# master_schematic.net
KiCad netlist of a schematic drawn in EAGLE
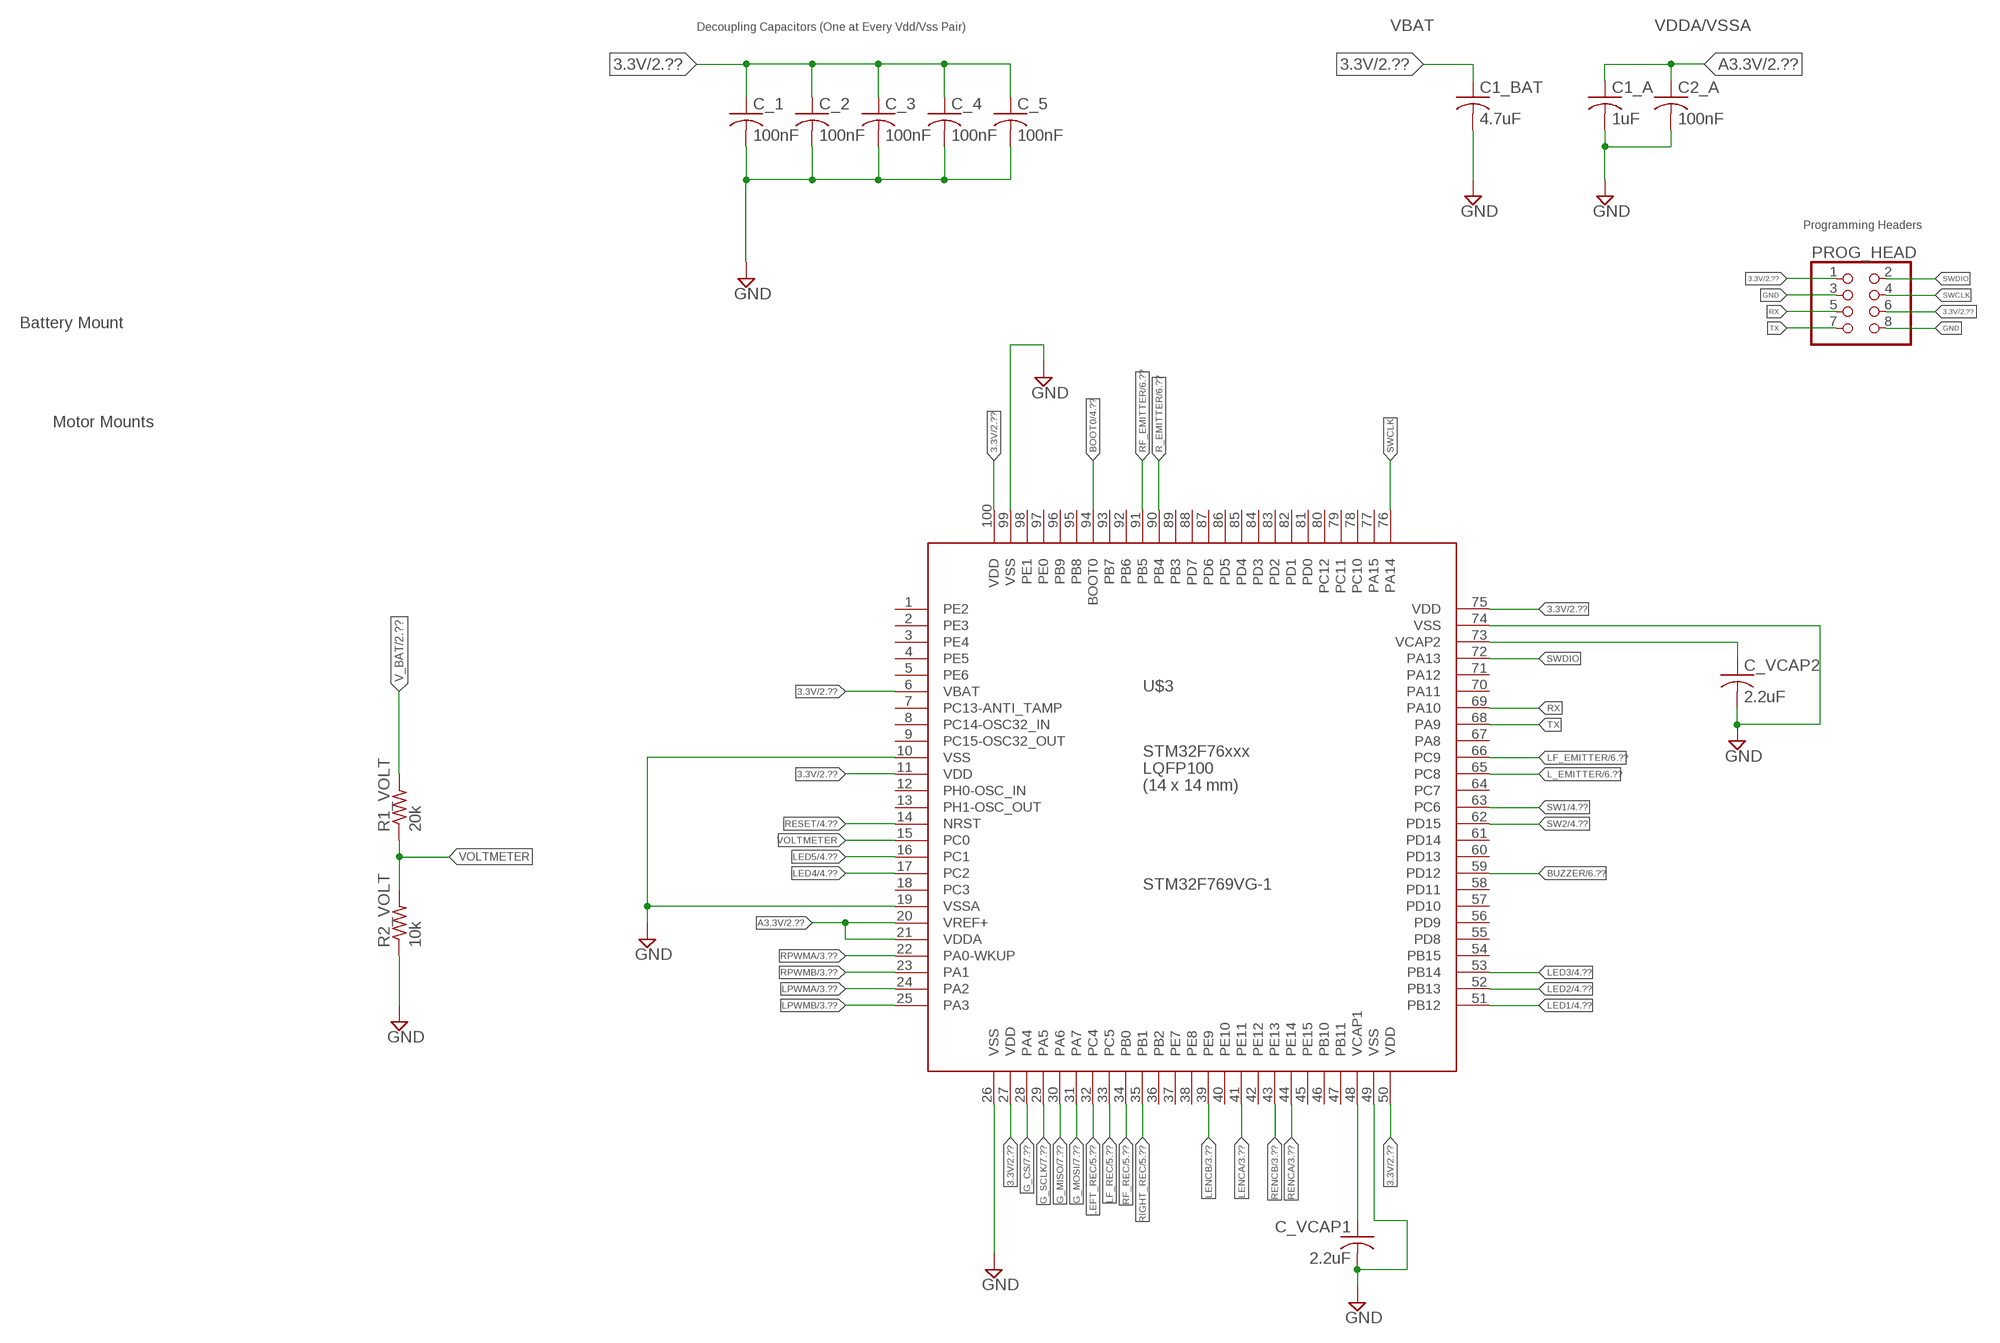
[diagram p0: schematic, sheet 1]
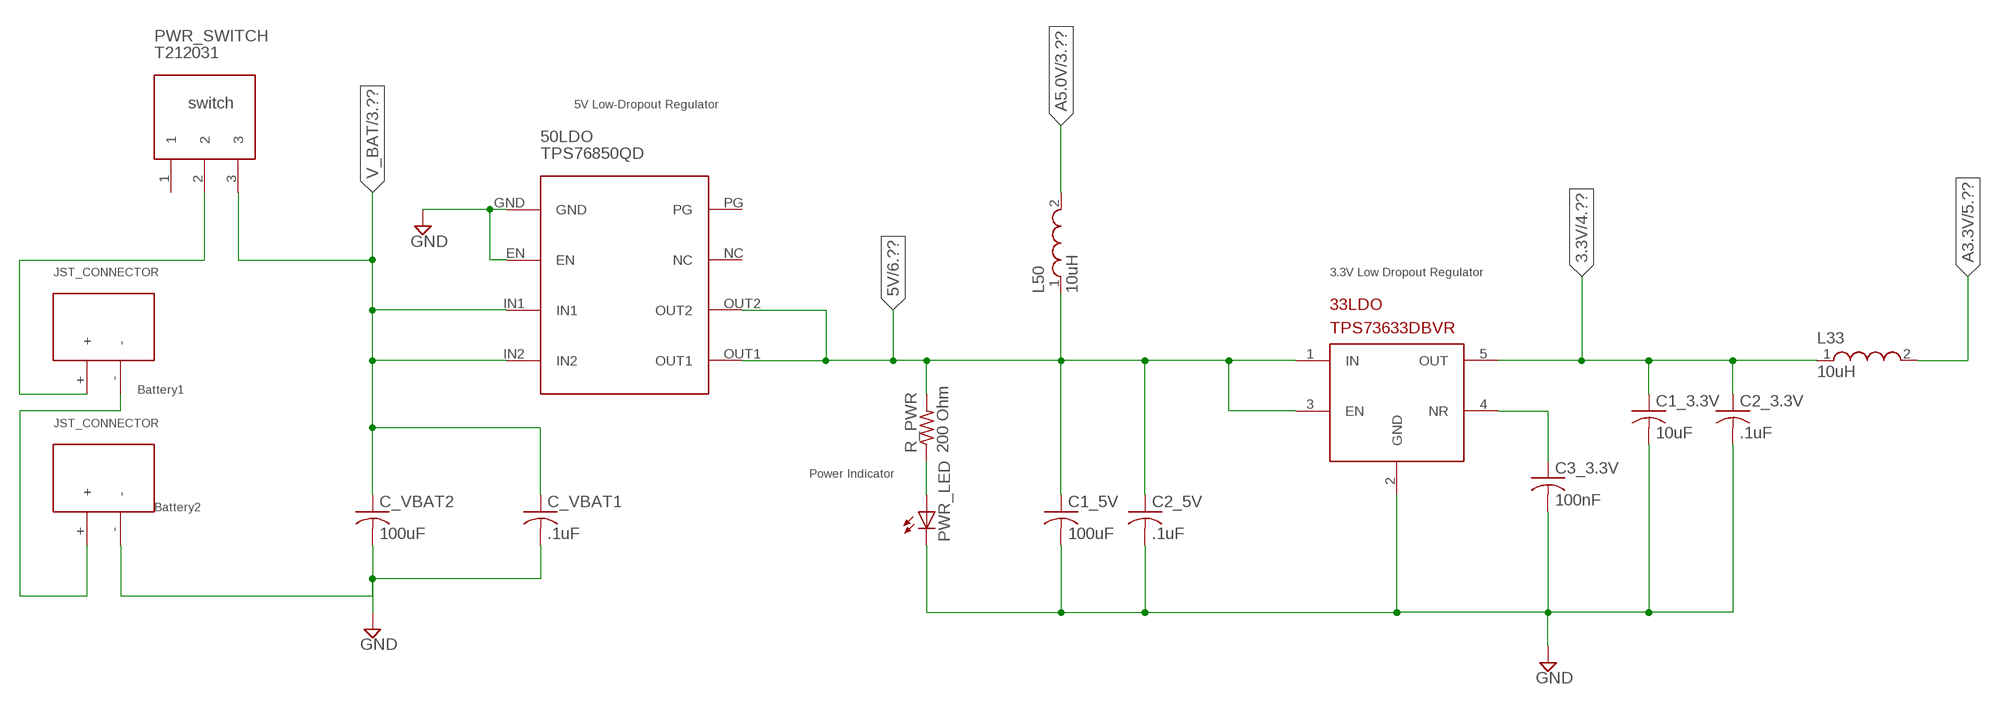
[diagram p1: schematic, sheet 2]
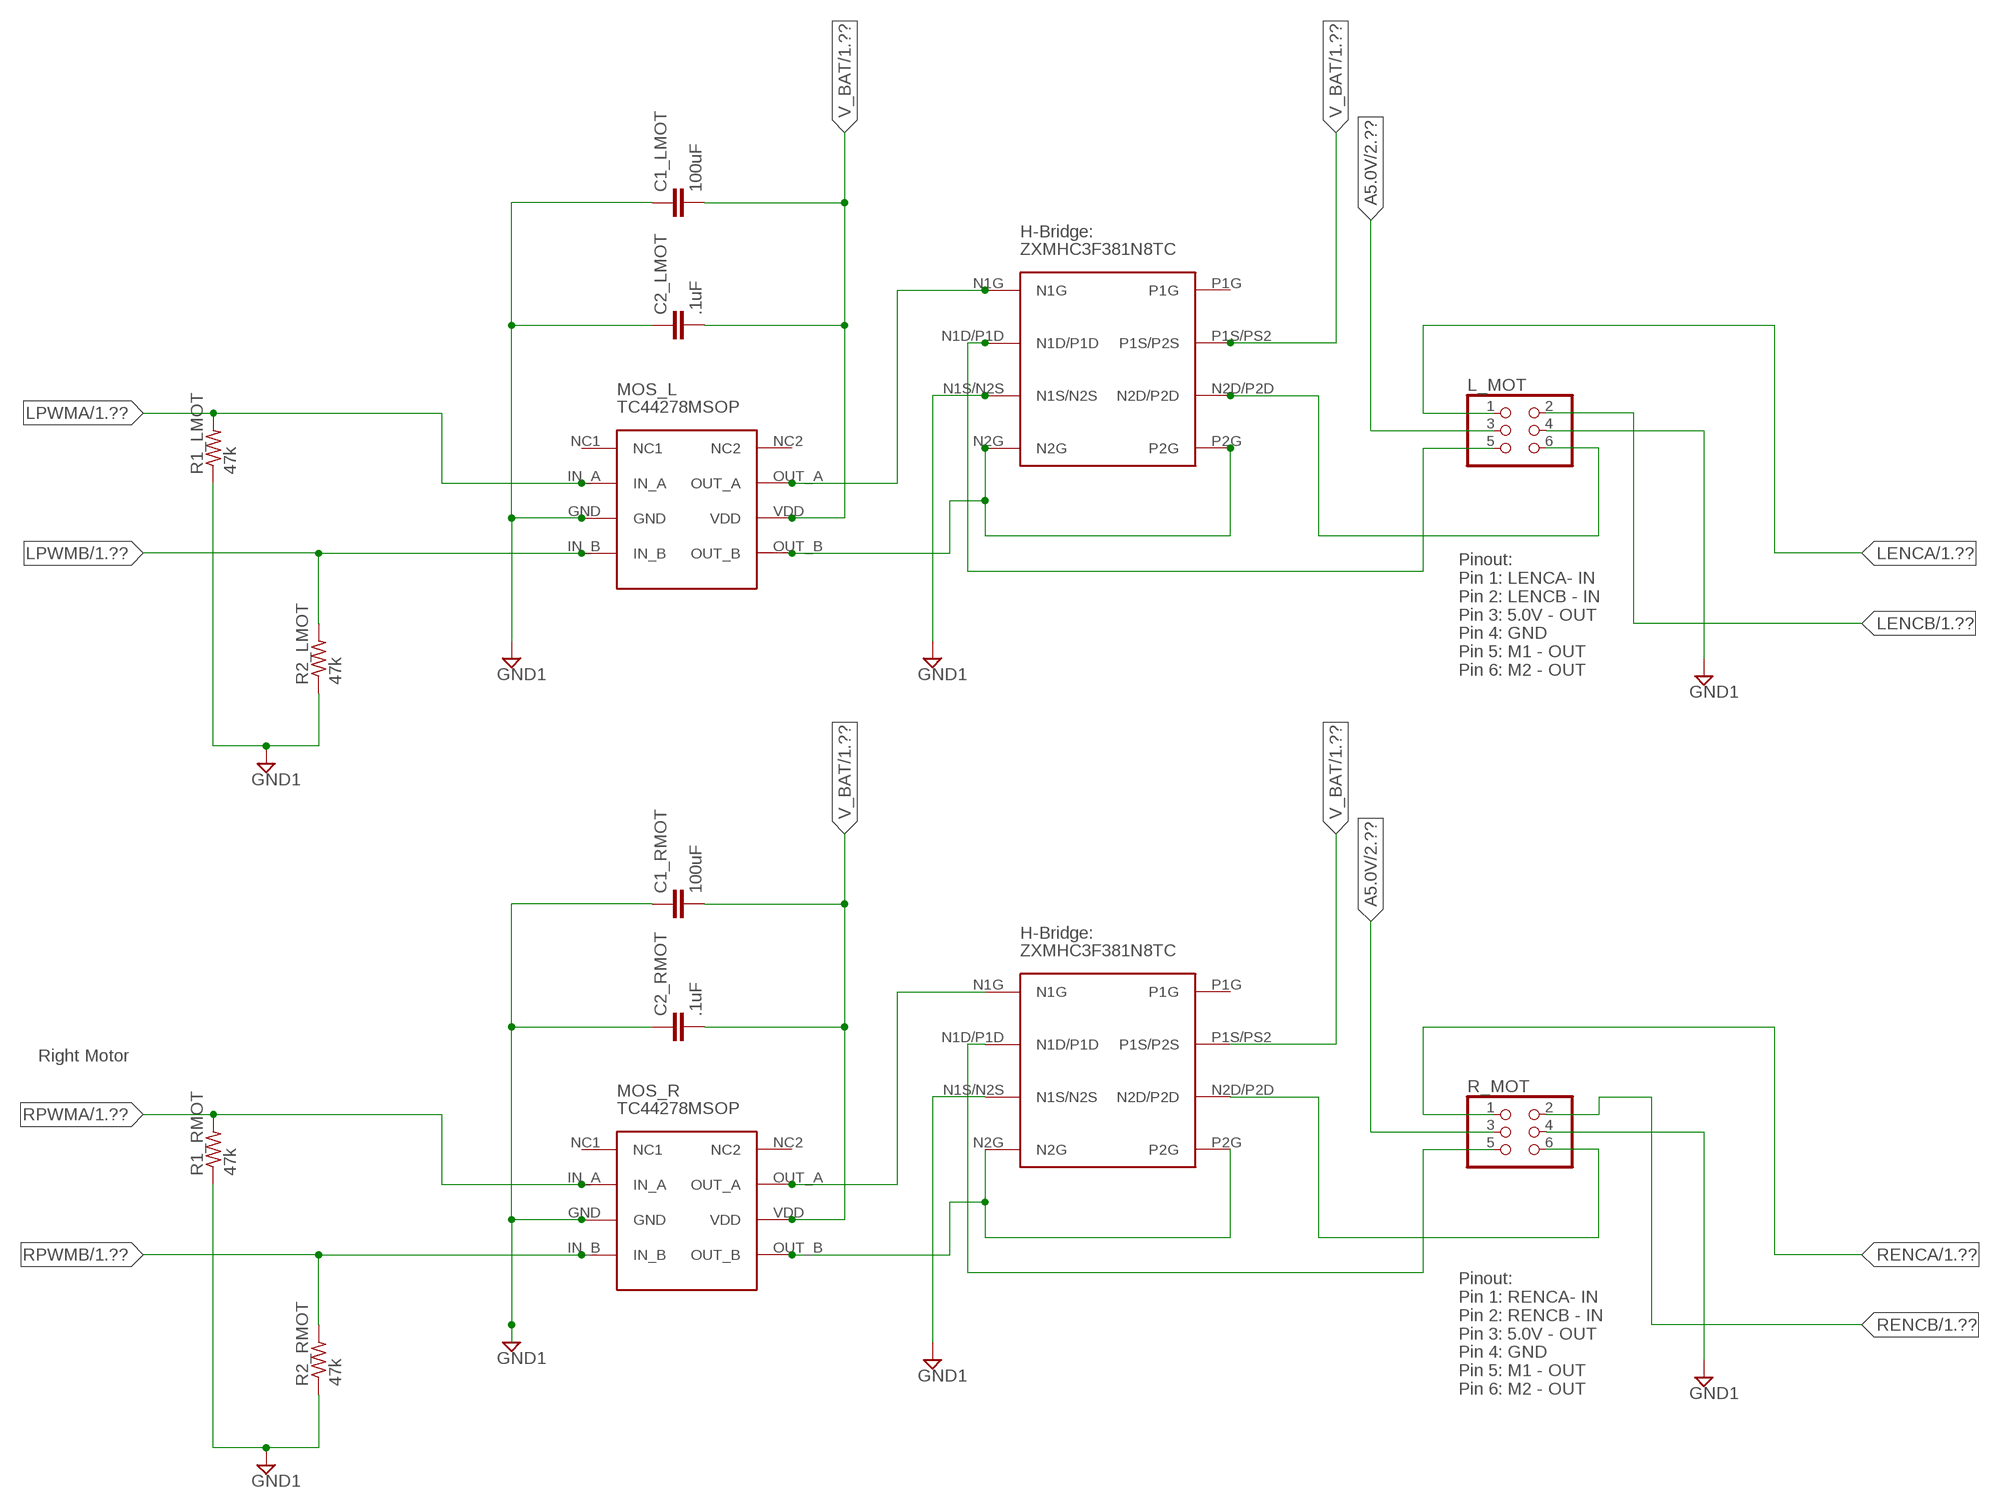
[diagram p2: schematic, sheet 3]
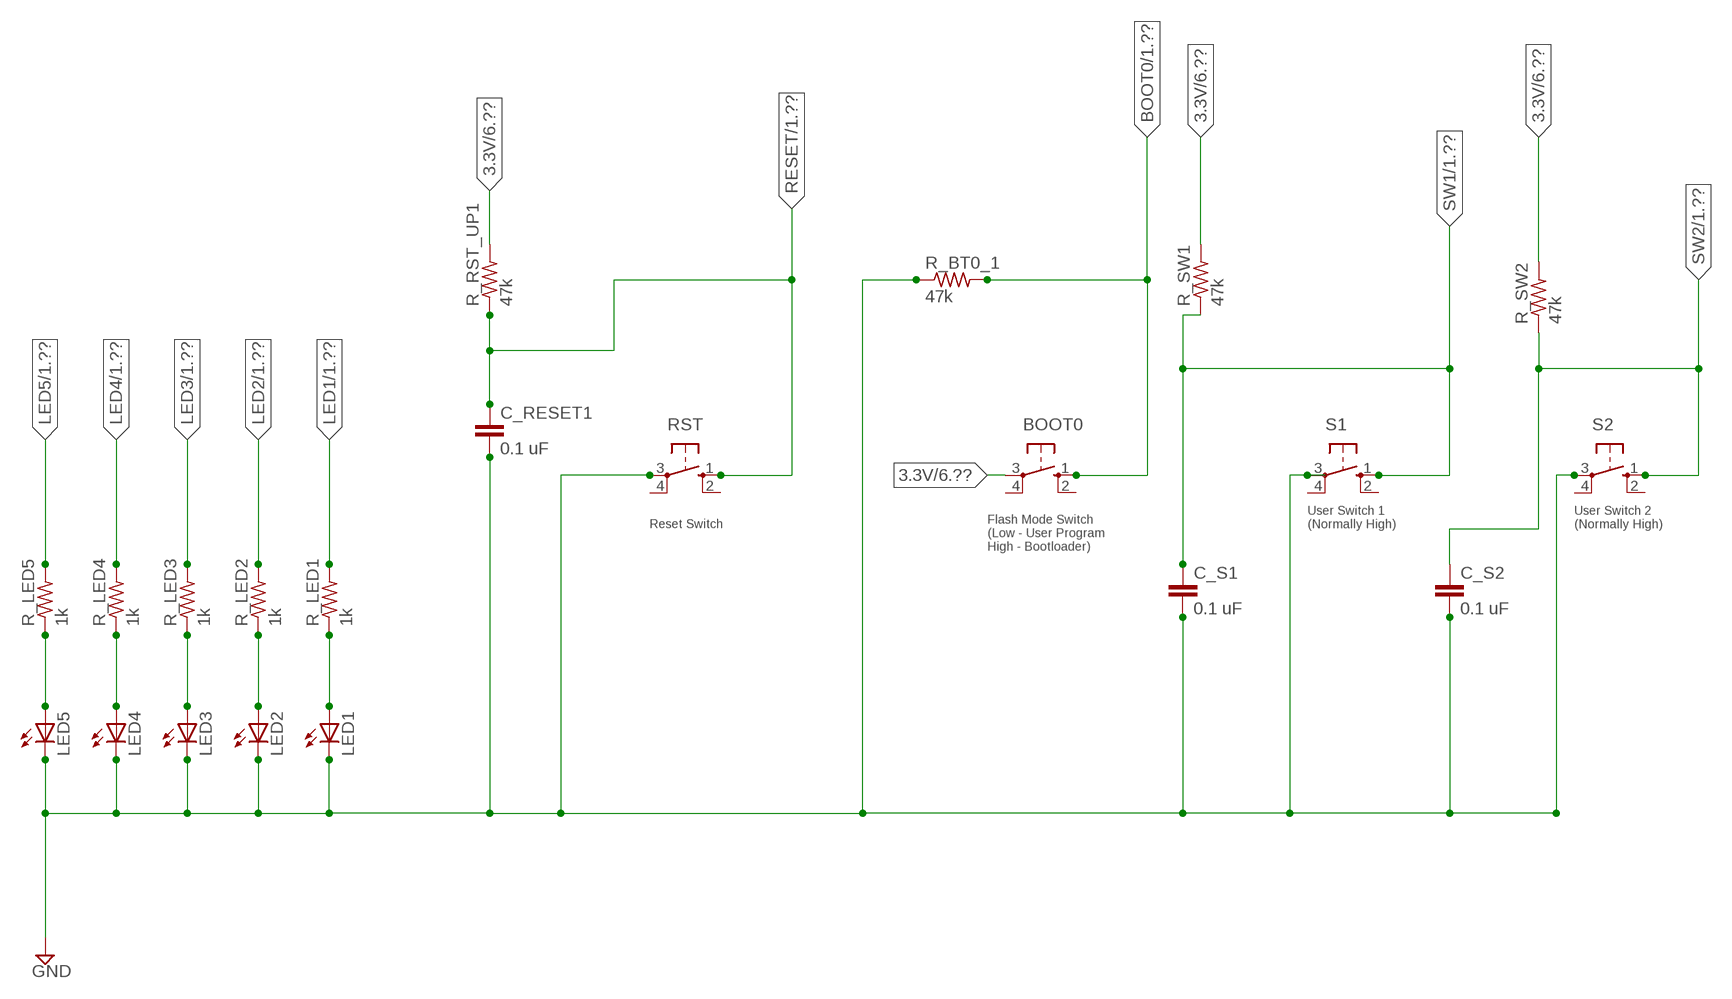
[diagram p3: schematic, sheet 4]
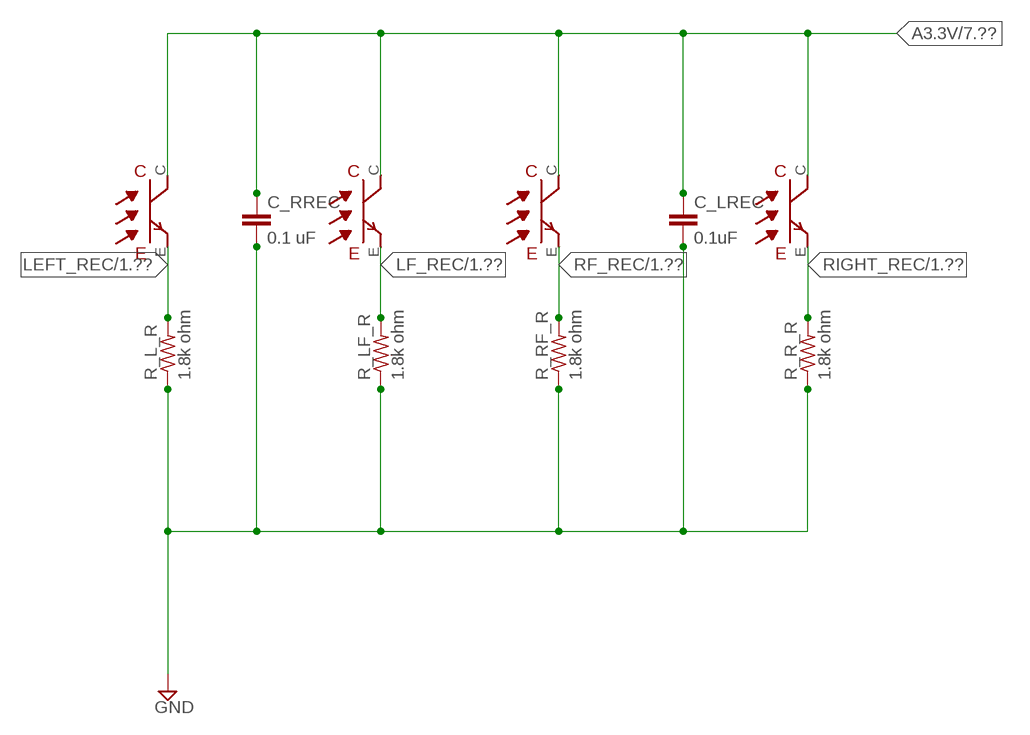
[diagram p4: schematic, sheet 5]
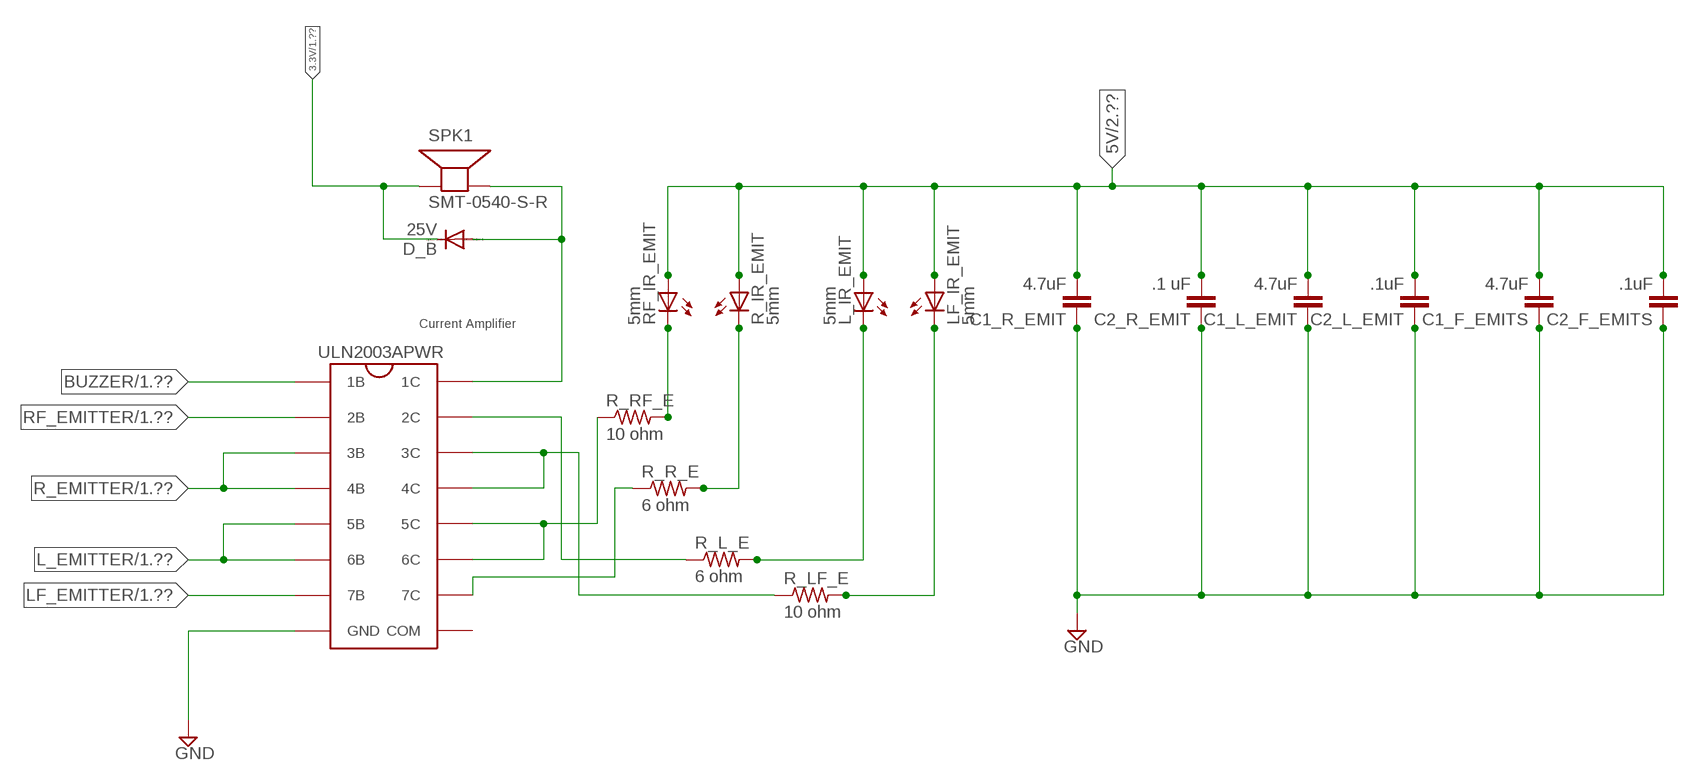
[diagram p5: schematic, sheet 6]
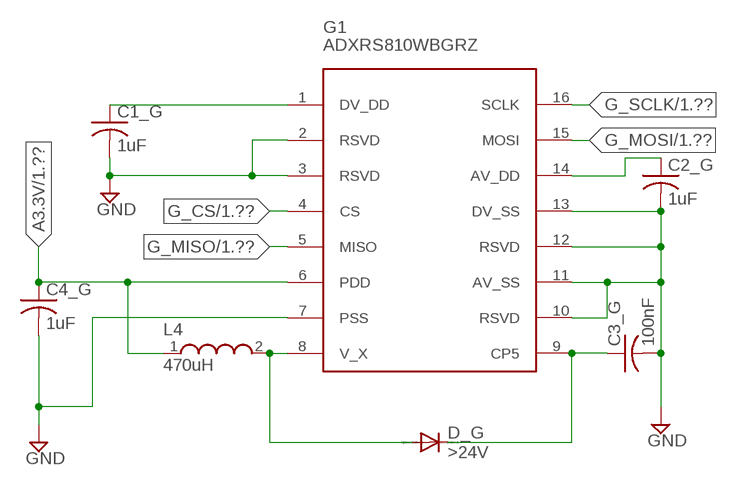
[diagram p6: schematic, sheet 7]

(export (version "E")
  (design (tool "Eeschema 10.0.6"))
  (components
    (comp (ref "33LDO")
      (value "TPS73633DBVR")
      (footprint "eagle-import:SOT23-DBV")
      (fields (field (name "MF") "Texas Instruments"))
      (libsource (lib "eagle-import") (part "TPS73633DBVR"))
    )
    (comp (ref "50LDO")
      (value "TPS76850QD")
      (footprint "eagle-import:8-SOIC(SMT)")
      (libsource (lib "eagle-import") (part "TPS76850"))
    )
    (comp (ref "C1_3.3V")
      (value "10uF")
      (footprint "eagle-import:C0603")
      (libsource (lib "eagle-import") (part "resistor_C-USC0603"))
    )
    (comp (ref "C1_5V")
      (value "100uF")
      (footprint "eagle-import:C0603")
      (libsource (lib "eagle-import") (part "resistor_C-USC0603"))
    )
    (comp (ref "C2_3.3V")
      (value ".1uF")
      (footprint "eagle-import:C0603")
      (libsource (lib "eagle-import") (part "resistor_C-USC0603"))
    )
    (comp (ref "C2_5V")
      (value ".1uF")
      (footprint "eagle-import:C0603")
      (libsource (lib "eagle-import") (part "resistor_C-USC0603"))
    )
    (comp (ref "C3_3.3V")
      (value "100nF")
      (footprint "eagle-import:C0603")
      (libsource (lib "eagle-import") (part "resistor_C-USC0603"))
    )
    (comp (ref "C_VBAT1")
      (value ".1uF")
      (footprint "eagle-import:C0603")
      (libsource (lib "eagle-import") (part "resistor_C-USC0603"))
    )
    (comp (ref "C_VBAT2")
      (value "100uF")
      (footprint "eagle-import:C0603")
      (libsource (lib "eagle-import") (part "resistor_C-USC0603"))
    )
    (comp (ref "L33")
      (value "10uH")
      (footprint "eagle-import:WE-MI_0805")
      (libsource (lib "eagle-import") (part "WE-MI_0805"))
    )
    (comp (ref "L50")
      (value "10uH")
      (footprint "eagle-import:WE-MI_0805")
      (libsource (lib "eagle-import") (part "WE-MI_0805"))
    )
    (comp (ref "PWR_LED")
      (value "LEDCHIPLED_0805")
      (footprint "eagle-import:CHIPLED_0805")
      (libsource (lib "eagle-import") (part "LEDCHIPLED_0805"))
    )
    (comp (ref "PWR_SWITCH")
      (value "T212031")
      (footprint "eagle-import:T212031")
      (libsource (lib "eagle-import") (part "T212031"))
    )
    (comp (ref "R_PWR")
      (value "200 Ohm")
      (footprint "eagle-import:R0603")
      (libsource (lib "eagle-import") (part "R-US_R0603"))
    )
    (comp (ref "U$7")
      (value "JST_CONNECTOR_FEMALE")
      (footprint "eagle-import:JST_CONNECTOR_FEMALE")
      (libsource (lib "eagle-import") (part "JST_CONNECTOR_FEMALE"))
    )
    (comp (ref "U$8")
      (value "JST_CONNECTOR_FEMALE")
      (footprint "eagle-import:JST_CONNECTOR_FEMALE")
      (libsource (lib "eagle-import") (part "JST_CONNECTOR_FEMALE"))
    )
    (comp (ref "C1_LMOT")
      (value "100uF")
      (footprint "eagle-import:C0603")
      (libsource (lib "eagle-import") (part "C-EUC0603"))
    )
    (comp (ref "C1_RMOT")
      (value "100uF")
      (footprint "eagle-import:C0603")
      (libsource (lib "eagle-import") (part "C-EUC0603"))
    )
    (comp (ref "C2_LMOT")
      (value ".1uF")
      (footprint "eagle-import:C0603")
      (libsource (lib "eagle-import") (part "C-EUC0603"))
    )
    (comp (ref "C2_RMOT")
      (value ".1uF")
      (footprint "eagle-import:C0603")
      (libsource (lib "eagle-import") (part "C-EUC0603"))
    )
    (comp (ref "HB_L")
      (value "ZXMHC3F381N8TC")
      (footprint "eagle-import:8-SOIC")
      (libsource (lib "eagle-import") (part "ZXMHC3F381N8TC"))
    )
    (comp (ref "HB_R")
      (value "ZXMHC3F381N8TC")
      (footprint "eagle-import:8-SOIC")
      (libsource (lib "eagle-import") (part "ZXMHC3F381N8TC"))
    )
    (comp (ref "L_MOT")
      (value "PINHD-2X3")
      (footprint "eagle-import:2X03")
      (libsource (lib "eagle-import") (part "PINHD-2X3"))
    )
    (comp (ref "MOS_L")
      (value "TC44278MSOP")
      (footprint "eagle-import:TC44278MSOP")
      (libsource (lib "eagle-import") (part "TC44278MSOP"))
    )
    (comp (ref "MOS_R")
      (value "TC44278MSOP")
      (footprint "eagle-import:TC44278MSOP")
      (libsource (lib "eagle-import") (part "TC44278MSOP"))
    )
    (comp (ref "R1_LMOT")
      (value "47k")
      (footprint "eagle-import:R0603")
      (libsource (lib "eagle-import") (part "R-US_R0603"))
    )
    (comp (ref "R1_RMOT")
      (value "47k")
      (footprint "eagle-import:R0603")
      (libsource (lib "eagle-import") (part "R-US_R0603"))
    )
    (comp (ref "R2_LMOT")
      (value "47k")
      (footprint "eagle-import:R0603")
      (libsource (lib "eagle-import") (part "R-US_R0603"))
    )
    (comp (ref "R2_RMOT")
      (value "47k")
      (footprint "eagle-import:R0603")
      (libsource (lib "eagle-import") (part "R-US_R0603"))
    )
    (comp (ref "R_MOT")
      (value "PINHD-2X3")
      (footprint "eagle-import:2X03")
      (libsource (lib "eagle-import") (part "PINHD-2X3"))
    )
    (comp (ref "C_LREC")
      (value "0.1uF")
      (footprint "eagle-import:C0603")
      (libsource (lib "eagle-import") (part "resistor_C-EUC0603"))
    )
    (comp (ref "C_RREC")
      (value "0.1 uF")
      (footprint "eagle-import:C0603")
      (libsource (lib "eagle-import") (part "resistor_C-EUC0603"))
    )
    (comp (ref "LF_REC")
      (value "RECEIVER")
      (footprint "eagle-import:RECEIVER")
      (libsource (lib "eagle-import") (part "RECEIVER"))
    )
    (comp (ref "L_REC")
      (value "RECEIVER")
      (footprint "eagle-import:RECEIVER")
      (libsource (lib "eagle-import") (part "RECEIVER"))
    )
    (comp (ref "RF_REC")
      (value "RECEIVER")
      (footprint "eagle-import:RECEIVER")
      (libsource (lib "eagle-import") (part "RECEIVER"))
    )
    (comp (ref "R_LF_R")
      (value "1.8k ohm")
      (footprint "eagle-import:R0603")
      (libsource (lib "eagle-import") (part "R-US_R0603"))
    )
    (comp (ref "R_L_R")
      (value "1.8k ohm")
      (footprint "eagle-import:R0603")
      (libsource (lib "eagle-import") (part "R-US_R0603"))
    )
    (comp (ref "R_REC")
      (value "RECEIVER")
      (footprint "eagle-import:RECEIVER")
      (libsource (lib "eagle-import") (part "RECEIVER"))
    )
    (comp (ref "R_RF_R")
      (value "1.8k ohm")
      (footprint "eagle-import:R0603")
      (libsource (lib "eagle-import") (part "R-US_R0603"))
    )
    (comp (ref "R_R_R")
      (value "1.8k ohm")
      (footprint "eagle-import:R0603")
      (libsource (lib "eagle-import") (part "R-US_R0603"))
    )
    (comp (ref "BOOT0")
      (value "10-XX")
      (footprint "eagle-import:B3F-10XX")
      (fields (field (name "MPN") "B3F-1000"))
      (libsource (lib "eagle-import") (part "10-XX"))
    )
    (comp (ref "C_RESET1")
      (value "0.1 uF")
      (footprint "eagle-import:C0603")
      (libsource (lib "eagle-import") (part "resistor_C-EUC0603"))
    )
    (comp (ref "C_S1")
      (value "0.1 uF")
      (footprint "eagle-import:C0603")
      (libsource (lib "eagle-import") (part "resistor_C-EUC0603"))
    )
    (comp (ref "C_S2")
      (value "0.1 uF")
      (footprint "eagle-import:C0603")
      (libsource (lib "eagle-import") (part "resistor_C-EUC0603"))
    )
    (comp (ref "LED1")
      (value "LEDCHIPLED_0805")
      (footprint "eagle-import:CHIPLED_0805")
      (libsource (lib "eagle-import") (part "LEDCHIPLED_0805"))
    )
    (comp (ref "LED2")
      (value "LEDCHIPLED_0805")
      (footprint "eagle-import:CHIPLED_0805")
      (libsource (lib "eagle-import") (part "LEDCHIPLED_0805"))
    )
    (comp (ref "LED3")
      (value "LEDCHIPLED_0805")
      (footprint "eagle-import:CHIPLED_0805")
      (libsource (lib "eagle-import") (part "LEDCHIPLED_0805"))
    )
    (comp (ref "LED4")
      (value "LEDCHIPLED_0805")
      (footprint "eagle-import:CHIPLED_0805")
      (libsource (lib "eagle-import") (part "LEDCHIPLED_0805"))
    )
    (comp (ref "LED5")
      (value "LEDCHIPLED_0805")
      (footprint "eagle-import:CHIPLED_0805")
      (libsource (lib "eagle-import") (part "LEDCHIPLED_0805"))
    )
    (comp (ref "RST")
      (value "10-XX")
      (footprint "eagle-import:B3F-10XX")
      (fields (field (name "MPN") "B3F-1000"))
      (libsource (lib "eagle-import") (part "10-XX"))
    )
    (comp (ref "R_BT0_1")
      (value "47k")
      (footprint "eagle-import:R0603")
      (libsource (lib "eagle-import") (part "R-US_R0603"))
    )
    (comp (ref "R_LED1")
      (value "1k")
      (footprint "eagle-import:R0603")
      (libsource (lib "eagle-import") (part "R-US_R0603"))
    )
    (comp (ref "R_LED2")
      (value "1k")
      (footprint "eagle-import:R0603")
      (libsource (lib "eagle-import") (part "R-US_R0603"))
    )
    (comp (ref "R_LED3")
      (value "1k")
      (footprint "eagle-import:R0603")
      (libsource (lib "eagle-import") (part "R-US_R0603"))
    )
    (comp (ref "R_LED4")
      (value "1k")
      (footprint "eagle-import:R0603")
      (libsource (lib "eagle-import") (part "R-US_R0603"))
    )
    (comp (ref "R_LED5")
      (value "1k")
      (footprint "eagle-import:R0603")
      (libsource (lib "eagle-import") (part "R-US_R0603"))
    )
    (comp (ref "R_RST_UP1")
      (value "47k")
      (footprint "eagle-import:R0603")
      (libsource (lib "eagle-import") (part "R-US_R0603"))
    )
    (comp (ref "R_SW1")
      (value "47k")
      (footprint "eagle-import:R0603")
      (libsource (lib "eagle-import") (part "R-US_R0603"))
    )
    (comp (ref "R_SW2")
      (value "47k")
      (footprint "eagle-import:R0603")
      (libsource (lib "eagle-import") (part "R-US_R0603"))
    )
    (comp (ref "S1")
      (value "10-XX")
      (footprint "eagle-import:B3F-10XX")
      (fields (field (name "MPN") "B3F-1000"))
      (libsource (lib "eagle-import") (part "10-XX"))
    )
    (comp (ref "S2")
      (value "10-XX")
      (footprint "eagle-import:B3F-10XX")
      (fields (field (name "MPN") "B3F-1000"))
      (libsource (lib "eagle-import") (part "10-XX"))
    )
    (comp (ref "C1_F_EMITS")
      (value "4.7uF")
      (footprint "eagle-import:C0603")
      (libsource (lib "eagle-import") (part "resistor_C-EUC0603"))
    )
    (comp (ref "C1_L_EMIT")
      (value "4.7uF")
      (footprint "eagle-import:C0603")
      (libsource (lib "eagle-import") (part "resistor_C-EUC0603"))
    )
    (comp (ref "C1_R_EMIT")
      (value "4.7uF")
      (footprint "eagle-import:C0603")
      (libsource (lib "eagle-import") (part "resistor_C-EUC0603"))
    )
    (comp (ref "C2_F_EMITS")
      (value ".1uF")
      (footprint "eagle-import:C0603")
      (libsource (lib "eagle-import") (part "resistor_C-EUC0603"))
    )
    (comp (ref "C2_L_EMIT")
      (value ".1uF")
      (footprint "eagle-import:C0603")
      (libsource (lib "eagle-import") (part "resistor_C-EUC0603"))
    )
    (comp (ref "C2_R_EMIT")
      (value ".1 uF")
      (footprint "eagle-import:C0603")
      (libsource (lib "eagle-import") (part "resistor_C-EUC0603"))
    )
    (comp (ref "D_B")
      (value "25V")
      (footprint "eagle-import:SOD123")
      (libsource (lib "eagle-import") (part "DIODE-SOD123"))
    )
    (comp (ref "LF_IR_EMIT")
      (value "5mm")
      (footprint "eagle-import:LED5MM")
      (libsource (lib "eagle-import") (part "LED5MM"))
    )
    (comp (ref "L_IR_EMIT")
      (value "5mm")
      (footprint "eagle-import:LED5MM")
      (libsource (lib "eagle-import") (part "LED5MM"))
    )
    (comp (ref "RF_IR_EMIT")
      (value "5mm")
      (footprint "eagle-import:LED5MM")
      (libsource (lib "eagle-import") (part "LED5MM"))
    )
    (comp (ref "R_IR_EMIT")
      (value "5mm")
      (footprint "eagle-import:LED5MM")
      (libsource (lib "eagle-import") (part "LED5MM"))
    )
    (comp (ref "R_LF_E")
      (value "10 ohm")
      (footprint "eagle-import:R0603")
      (libsource (lib "eagle-import") (part "R-US_R0603"))
    )
    (comp (ref "R_L_E")
      (value "6 ohm")
      (footprint "eagle-import:R0603")
      (libsource (lib "eagle-import") (part "R-US_R0603"))
    )
    (comp (ref "R_RF_E")
      (value "10 ohm")
      (footprint "eagle-import:R0603")
      (libsource (lib "eagle-import") (part "R-US_R0603"))
    )
    (comp (ref "R_R_E")
      (value "6 ohm")
      (footprint "eagle-import:R0603")
      (libsource (lib "eagle-import") (part "R-US_R0603"))
    )
    (comp (ref "SPK1")
      (value "SMT-0540-S-R")
      (footprint "eagle-import:SMT-0540-S-R")
      (fields (field (name "MF") "PUI Audio"))
      (libsource (lib "eagle-import") (part "SMT-0540-S-R"))
    )
    (comp (ref "U$9")
      (value "ULN2003APWR")
      (footprint "eagle-import:ULN2003APWR")
      (libsource (lib "eagle-import") (part "ULN2003APWR"))
    )
    (comp (ref "C1_G")
      (value "1uF")
      (footprint "eagle-import:C0603")
      (libsource (lib "eagle-import") (part "C-USC0603"))
    )
    (comp (ref "C2_G")
      (value "1uF")
      (footprint "eagle-import:C0603")
      (libsource (lib "eagle-import") (part "C-USC0603"))
    )
    (comp (ref "C3_G")
      (value "100nF")
      (footprint "eagle-import:C0603")
      (libsource (lib "eagle-import") (part "C-USC0603"))
    )
    (comp (ref "C4_G")
      (value "1uF")
      (footprint "eagle-import:C0603")
      (libsource (lib "eagle-import") (part "C-USC0603"))
    )
    (comp (ref "D_G")
      (value ">24V")
      (footprint "eagle-import:SOD123")
      (libsource (lib "eagle-import") (part "DIODE-SOD123"))
    )
    (comp (ref "G1")
      (value "ADXRS810")
      (footprint "eagle-import:SOIC-16")
      (libsource (lib "eagle-import") (part "ADXRS810"))
    )
    (comp (ref "L4")
      (value "470uH")
      (footprint "eagle-import:WE-MI_0805")
      (libsource (lib "eagle-import") (part "WE-MI_0805"))
    )
    (comp (ref "C1_A")
      (value "1uF")
      (footprint "eagle-import:C0603")
      (libsource (lib "eagle-import") (part "C-USC0603"))
    )
    (comp (ref "C1_BAT")
      (value "4.7uF")
      (footprint "eagle-import:C0603")
      (libsource (lib "eagle-import") (part "C-USC0603"))
    )
    (comp (ref "C2_A")
      (value "100nF")
      (footprint "eagle-import:C0603")
      (libsource (lib "eagle-import") (part "C-USC0603"))
    )
    (comp (ref "C_1")
      (value "100nF")
      (footprint "eagle-import:C0603")
      (libsource (lib "eagle-import") (part "C-USC0603"))
    )
    (comp (ref "C_2")
      (value "100nF")
      (footprint "eagle-import:C0603")
      (libsource (lib "eagle-import") (part "C-USC0603"))
    )
    (comp (ref "C_3")
      (value "100nF")
      (footprint "eagle-import:C0603")
      (libsource (lib "eagle-import") (part "C-USC0603"))
    )
    (comp (ref "C_4")
      (value "100nF")
      (footprint "eagle-import:C0603")
      (libsource (lib "eagle-import") (part "C-USC0603"))
    )
    (comp (ref "C_5")
      (value "100nF")
      (footprint "eagle-import:C0603")
      (libsource (lib "eagle-import") (part "C-USC0603"))
    )
    (comp (ref "C_VCAP1")
      (value "2.2uF")
      (footprint "eagle-import:C0603")
      (libsource (lib "eagle-import") (part "C-USC0603"))
    )
    (comp (ref "C_VCAP2")
      (value "2.2uF")
      (footprint "eagle-import:C0603")
      (libsource (lib "eagle-import") (part "C-USC0603"))
    )
    (comp (ref "PROG_HEAD")
      (value "PINHD-2X4")
      (footprint "eagle-import:2X04")
      (libsource (lib "eagle-import") (part "PINHD-2X4"))
    )
    (comp (ref "R1_VOLT")
      (value "20k")
      (footprint "eagle-import:R0603")
      (libsource (lib "eagle-import") (part "R-US_R0603"))
    )
    (comp (ref "R2_VOLT")
      (value "10k")
      (footprint "eagle-import:R0603")
      (libsource (lib "eagle-import") (part "R-US_R0603"))
    )
    (comp (ref "U$1")
      (value "BAT")
      (footprint "eagle-import:BAT_FOOTPRINT")
      (libsource (lib "eagle-import") (part "BAT"))
    )
    (comp (ref "U$2")
      (value "MOTOR")
      (footprint "eagle-import:MOTOR_MOUNT")
      (libsource (lib "eagle-import") (part "MOTOR"))
    )
    (comp (ref "U$3")
      (value "STM32F769VG-1")
      (footprint "eagle-import:LQFP100")
      (libsource (lib "eagle-import") (part "STM32F769VG-1"))
    )
    (comp (ref "U$5")
      (value "MOTOR")
      (footprint "eagle-import:MOTOR_MOUNT")
      (libsource (lib "eagle-import") (part "MOTOR"))
    )
  )
  (nets
    (net (code "1") (name "3.3V") (class "Default")
      (node (ref "33LDO") (pin "5") (pinfunction "OUT_5") (pintype "bidirectional"))
      (node (ref "BOOT0") (pin "3") (pinfunction "P_3") (pintype "passive"))
      (node (ref "C1_3.3V") (pin "1") (pinfunction "1_1") (pintype "passive"))
      (node (ref "C1_BAT") (pin "1") (pinfunction "1_1") (pintype "passive"))
      (node (ref "C2_3.3V") (pin "1") (pinfunction "1_1") (pintype "passive"))
      (node (ref "C_1") (pin "1") (pinfunction "1_1") (pintype "passive"))
      (node (ref "C_2") (pin "1") (pinfunction "1_1") (pintype "passive"))
      (node (ref "C_3") (pin "1") (pinfunction "1_1") (pintype "passive"))
      (node (ref "C_4") (pin "1") (pinfunction "1_1") (pintype "passive"))
      (node (ref "C_5") (pin "1") (pinfunction "1_1") (pintype "passive"))
      (node (ref "D_B") (pin "C") (pinfunction "C_C") (pintype "passive"))
      (node (ref "L33") (pin "1") (pinfunction "1_1") (pintype "passive"))
      (node (ref "PROG_HEAD") (pin "1") (pinfunction "1_1") (pintype "passive"))
      (node (ref "PROG_HEAD") (pin "6") (pinfunction "6_6") (pintype "passive"))
      (node (ref "R_RST_UP1") (pin "2") (pinfunction "2_2") (pintype "passive"))
      (node (ref "R_SW1") (pin "2") (pinfunction "2_2") (pintype "passive"))
      (node (ref "R_SW2") (pin "2") (pinfunction "2_2") (pintype "passive"))
      (node (ref "SPK1") (pin "-") (pinfunction "+_-") (pintype "passive"))
      (node (ref "U$3") (pin "100") (pinfunction "VDD_100") (pintype "bidirectional"))
      (node (ref "U$3") (pin "11") (pinfunction "VDD_11") (pintype "bidirectional"))
      (node (ref "U$3") (pin "27") (pinfunction "VDD_27") (pintype "bidirectional"))
      (node (ref "U$3") (pin "50") (pinfunction "VDD_50") (pintype "bidirectional"))
      (node (ref "U$3") (pin "6") (pinfunction "VBAT_6") (pintype "bidirectional"))
      (node (ref "U$3") (pin "75") (pinfunction "VDD_75") (pintype "bidirectional"))
    )
    (net (code "2") (name "5V") (class "Default")
      (node (ref "33LDO") (pin "1") (pinfunction "IN_1") (pintype "bidirectional"))
      (node (ref "33LDO") (pin "3") (pinfunction "EN_3") (pintype "bidirectional"))
      (node (ref "50LDO") (pin "OUT1") (pinfunction "OUT1_OUT1") (pintype "bidirectional"))
      (node (ref "50LDO") (pin "OUT2") (pinfunction "OUT2_OUT2") (pintype "bidirectional"))
      (node (ref "C1_5V") (pin "1") (pinfunction "1_1") (pintype "passive"))
      (node (ref "C1_F_EMITS") (pin "2") (pinfunction "2_2") (pintype "passive"))
      (node (ref "C1_L_EMIT") (pin "2") (pinfunction "2_2") (pintype "passive"))
      (node (ref "C1_R_EMIT") (pin "2") (pinfunction "2_2") (pintype "passive"))
      (node (ref "C2_5V") (pin "1") (pinfunction "1_1") (pintype "passive"))
      (node (ref "C2_F_EMITS") (pin "2") (pinfunction "2_2") (pintype "passive"))
      (node (ref "C2_L_EMIT") (pin "2") (pinfunction "2_2") (pintype "passive"))
      (node (ref "C2_R_EMIT") (pin "2") (pinfunction "2_2") (pintype "passive"))
      (node (ref "L50") (pin "1") (pinfunction "1_1") (pintype "passive"))
      (node (ref "LF_IR_EMIT") (pin "A") (pinfunction "A_A") (pintype "passive"))
      (node (ref "L_IR_EMIT") (pin "A") (pinfunction "A_A") (pintype "passive"))
      (node (ref "RF_IR_EMIT") (pin "A") (pinfunction "A_A") (pintype "passive"))
      (node (ref "R_IR_EMIT") (pin "A") (pinfunction "A_A") (pintype "passive"))
      (node (ref "R_PWR") (pin "2") (pinfunction "2_2") (pintype "passive"))
    )
    (net (code "3") (name "A3.3V") (class "Default")
      (node (ref "C1_A") (pin "1") (pinfunction "1_1") (pintype "passive"))
      (node (ref "C2_A") (pin "1") (pinfunction "1_1") (pintype "passive"))
      (node (ref "C4_G") (pin "1") (pinfunction "1_1") (pintype "passive"))
      (node (ref "C_LREC") (pin "1") (pinfunction "1_1") (pintype "passive"))
      (node (ref "C_RREC") (pin "1") (pinfunction "1_1") (pintype "passive"))
      (node (ref "G1") (pin "6") (pinfunction "PDD_6") (pintype "bidirectional"))
      (node (ref "L33") (pin "2") (pinfunction "2_2") (pintype "passive"))
      (node (ref "L4") (pin "1") (pinfunction "1_1") (pintype "passive"))
      (node (ref "LF_REC") (pin "C") (pinfunction "C_C") (pintype "bidirectional"))
      (node (ref "L_REC") (pin "C") (pinfunction "C_C") (pintype "bidirectional"))
      (node (ref "RF_REC") (pin "C") (pinfunction "C_C") (pintype "bidirectional"))
      (node (ref "R_REC") (pin "C") (pinfunction "C_C") (pintype "bidirectional"))
      (node (ref "U$3") (pin "20") (pinfunction "VREF+_20") (pintype "bidirectional"))
      (node (ref "U$3") (pin "21") (pinfunction "VDDA_21") (pintype "bidirectional"))
    )
    (net (code "4") (name "A5.0V") (class "Default")
      (node (ref "L50") (pin "2") (pinfunction "2_2") (pintype "passive"))
      (node (ref "L_MOT") (pin "3") (pinfunction "3_3") (pintype "passive"))
      (node (ref "R_MOT") (pin "3") (pinfunction "3_3") (pintype "passive"))
    )
    (net (code "5") (name "BOOT0") (class "Default")
      (node (ref "BOOT0") (pin "1") (pinfunction "S_1") (pintype "passive"))
      (node (ref "R_BT0_1") (pin "2") (pinfunction "2_2") (pintype "passive"))
      (node (ref "U$3") (pin "94") (pinfunction "BOOT0_94") (pintype "bidirectional"))
    )
    (net (code "6") (name "BUZZER") (class "Default")
      (node (ref "U$3") (pin "59") (pinfunction "PD12_59") (pintype "bidirectional"))
      (node (ref "U$9") (pin "1B") (pinfunction "1B_1B") (pintype "bidirectional"))
    )
    (net (code "7") (name "GND") (class "Default")
      (node (ref "33LDO") (pin "2") (pinfunction "GND_2") (pintype "bidirectional"))
      (node (ref "50LDO") (pin "EN") (pinfunction "EN_EN") (pintype "bidirectional"))
      (node (ref "50LDO") (pin "GND") (pinfunction "GND_GND") (pintype "bidirectional"))
      (node (ref "C1_3.3V") (pin "2") (pinfunction "2_2") (pintype "passive"))
      (node (ref "C1_5V") (pin "2") (pinfunction "2_2") (pintype "passive"))
      (node (ref "C1_A") (pin "2") (pinfunction "2_2") (pintype "passive"))
      (node (ref "C1_BAT") (pin "2") (pinfunction "2_2") (pintype "passive"))
      (node (ref "C1_F_EMITS") (pin "1") (pinfunction "1_1") (pintype "passive"))
      (node (ref "C1_G") (pin "2") (pinfunction "2_2") (pintype "passive"))
      (node (ref "C1_LMOT") (pin "1") (pinfunction "1_1") (pintype "passive"))
      (node (ref "C1_L_EMIT") (pin "1") (pinfunction "1_1") (pintype "passive"))
      (node (ref "C1_RMOT") (pin "1") (pinfunction "1_1") (pintype "passive"))
      (node (ref "C1_R_EMIT") (pin "1") (pinfunction "1_1") (pintype "passive"))
      (node (ref "C2_3.3V") (pin "2") (pinfunction "2_2") (pintype "passive"))
      (node (ref "C2_5V") (pin "2") (pinfunction "2_2") (pintype "passive"))
      (node (ref "C2_A") (pin "2") (pinfunction "2_2") (pintype "passive"))
      (node (ref "C2_F_EMITS") (pin "1") (pinfunction "1_1") (pintype "passive"))
      (node (ref "C2_G") (pin "2") (pinfunction "2_2") (pintype "passive"))
      (node (ref "C2_LMOT") (pin "1") (pinfunction "1_1") (pintype "passive"))
      (node (ref "C2_L_EMIT") (pin "1") (pinfunction "1_1") (pintype "passive"))
      (node (ref "C2_RMOT") (pin "1") (pinfunction "1_1") (pintype "passive"))
      (node (ref "C2_R_EMIT") (pin "1") (pinfunction "1_1") (pintype "passive"))
      (node (ref "C3_3.3V") (pin "2") (pinfunction "2_2") (pintype "passive"))
      (node (ref "C3_G") (pin "2") (pinfunction "2_2") (pintype "passive"))
      (node (ref "C4_G") (pin "2") (pinfunction "2_2") (pintype "passive"))
      (node (ref "C_1") (pin "2") (pinfunction "2_2") (pintype "passive"))
      (node (ref "C_2") (pin "2") (pinfunction "2_2") (pintype "passive"))
      (node (ref "C_3") (pin "2") (pinfunction "2_2") (pintype "passive"))
      (node (ref "C_4") (pin "2") (pinfunction "2_2") (pintype "passive"))
      (node (ref "C_5") (pin "2") (pinfunction "2_2") (pintype "passive"))
      (node (ref "C_LREC") (pin "2") (pinfunction "2_2") (pintype "passive"))
      (node (ref "C_RESET1") (pin "2") (pinfunction "2_2") (pintype "passive"))
      (node (ref "C_RREC") (pin "2") (pinfunction "2_2") (pintype "passive"))
      (node (ref "C_S1") (pin "2") (pinfunction "2_2") (pintype "passive"))
      (node (ref "C_S2") (pin "2") (pinfunction "2_2") (pintype "passive"))
      (node (ref "C_VBAT1") (pin "2") (pinfunction "2_2") (pintype "passive"))
      (node (ref "C_VBAT2") (pin "2") (pinfunction "2_2") (pintype "passive"))
      (node (ref "C_VCAP1") (pin "2") (pinfunction "2_2") (pintype "passive"))
      (node (ref "C_VCAP2") (pin "2") (pinfunction "2_2") (pintype "passive"))
      (node (ref "G1") (pin "10") (pinfunction "RSVD_10") (pintype "bidirectional"))
      (node (ref "G1") (pin "11") (pinfunction "AV_SS_11") (pintype "bidirectional"))
      (node (ref "G1") (pin "12") (pinfunction "RSVD_12") (pintype "bidirectional"))
      (node (ref "G1") (pin "13") (pinfunction "DV_SS_13") (pintype "bidirectional"))
      (node (ref "G1") (pin "2") (pinfunction "RSVD_2") (pintype "bidirectional"))
      (node (ref "G1") (pin "3") (pinfunction "RSVD_3") (pintype "bidirectional"))
      (node (ref "G1") (pin "7") (pinfunction "PSS_7") (pintype "bidirectional"))
      (node (ref "HB_L") (pin "N1S/N2S") (pinfunction "N1S/N2S_N1S/N2S") (pintype "bidirectional"))
      (node (ref "HB_R") (pin "N1S/N2S") (pinfunction "N1S/N2S_N1S/N2S") (pintype "bidirectional"))
      (node (ref "LED1") (pin "C") (pinfunction "C_C") (pintype "passive"))
      (node (ref "LED2") (pin "C") (pinfunction "C_C") (pintype "passive"))
      (node (ref "LED3") (pin "C") (pinfunction "C_C") (pintype "passive"))
      (node (ref "LED4") (pin "C") (pinfunction "C_C") (pintype "passive"))
      (node (ref "LED5") (pin "C") (pinfunction "C_C") (pintype "passive"))
      (node (ref "L_MOT") (pin "4") (pinfunction "4_4") (pintype "passive"))
      (node (ref "MOS_L") (pin "GND") (pinfunction "GND_GND") (pintype "bidirectional"))
      (node (ref "MOS_R") (pin "GND") (pinfunction "GND_GND") (pintype "bidirectional"))
      (node (ref "PROG_HEAD") (pin "3") (pinfunction "3_3") (pintype "passive"))
      (node (ref "PROG_HEAD") (pin "8") (pinfunction "8_8") (pintype "passive"))
      (node (ref "PWR_LED") (pin "C") (pinfunction "C_C") (pintype "passive"))
      (node (ref "R1_LMOT") (pin "1") (pinfunction "1_1") (pintype "passive"))
      (node (ref "R1_RMOT") (pin "1") (pinfunction "1_1") (pintype "passive"))
      (node (ref "R2_LMOT") (pin "1") (pinfunction "1_1") (pintype "passive"))
      (node (ref "R2_RMOT") (pin "1") (pinfunction "1_1") (pintype "passive"))
      (node (ref "R2_VOLT") (pin "1") (pinfunction "1_1") (pintype "passive"))
      (node (ref "RST") (pin "3") (pinfunction "P_3") (pintype "passive"))
      (node (ref "R_BT0_1") (pin "1") (pinfunction "1_1") (pintype "passive"))
      (node (ref "R_LF_R") (pin "1") (pinfunction "1_1") (pintype "passive"))
      (node (ref "R_L_R") (pin "1") (pinfunction "1_1") (pintype "passive"))
      (node (ref "R_MOT") (pin "4") (pinfunction "4_4") (pintype "passive"))
      (node (ref "R_RF_R") (pin "1") (pinfunction "1_1") (pintype "passive"))
      (node (ref "R_R_R") (pin "1") (pinfunction "1_1") (pintype "passive"))
      (node (ref "S1") (pin "3") (pinfunction "P_3") (pintype "passive"))
      (node (ref "S2") (pin "3") (pinfunction "P_3") (pintype "passive"))
      (node (ref "U$3") (pin "10") (pinfunction "VSS_10") (pintype "bidirectional"))
      (node (ref "U$3") (pin "19") (pinfunction "VSSA_19") (pintype "bidirectional"))
      (node (ref "U$3") (pin "26") (pinfunction "VSS_26") (pintype "bidirectional"))
      (node (ref "U$3") (pin "49") (pinfunction "VSS_49") (pintype "bidirectional"))
      (node (ref "U$3") (pin "74") (pinfunction "VSS_74") (pintype "bidirectional"))
      (node (ref "U$3") (pin "99") (pinfunction "VSS_99") (pintype "bidirectional"))
      (node (ref "U$8") (pin "-") (pinfunction "-_-") (pintype "bidirectional"))
      (node (ref "U$9") (pin "GND") (pinfunction "GND_GND") (pintype "bidirectional"))
    )
    (net (code "8") (name "G_CS") (class "Default")
      (node (ref "G1") (pin "4") (pinfunction "CS_4") (pintype "bidirectional"))
      (node (ref "U$3") (pin "28") (pinfunction "PA4_28") (pintype "bidirectional"))
    )
    (net (code "9") (name "G_MISO") (class "Default")
      (node (ref "G1") (pin "5") (pinfunction "MISO_5") (pintype "bidirectional"))
      (node (ref "U$3") (pin "30") (pinfunction "PA6_30") (pintype "bidirectional"))
    )
    (net (code "10") (name "G_MOSI") (class "Default")
      (node (ref "G1") (pin "15") (pinfunction "MOSI_15") (pintype "bidirectional"))
      (node (ref "U$3") (pin "31") (pinfunction "PA7_31") (pintype "bidirectional"))
    )
    (net (code "11") (name "G_SCLK") (class "Default")
      (node (ref "G1") (pin "16") (pinfunction "SCLK_16") (pintype "bidirectional"))
      (node (ref "U$3") (pin "29") (pinfunction "PA5_29") (pintype "bidirectional"))
    )
    (net (code "12") (name "LED1") (class "Default")
      (node (ref "R_LED1") (pin "2") (pinfunction "2_2") (pintype "passive"))
      (node (ref "U$3") (pin "51") (pinfunction "PB12_51") (pintype "bidirectional"))
    )
    (net (code "13") (name "LED2") (class "Default")
      (node (ref "R_LED2") (pin "2") (pinfunction "2_2") (pintype "passive"))
      (node (ref "U$3") (pin "52") (pinfunction "PB13_52") (pintype "bidirectional"))
    )
    (net (code "14") (name "LED3") (class "Default")
      (node (ref "R_LED3") (pin "2") (pinfunction "2_2") (pintype "passive"))
      (node (ref "U$3") (pin "53") (pinfunction "PB14_53") (pintype "bidirectional"))
    )
    (net (code "15") (name "LED4") (class "Default")
      (node (ref "R_LED4") (pin "2") (pinfunction "2_2") (pintype "passive"))
      (node (ref "U$3") (pin "17") (pinfunction "PC2_17") (pintype "bidirectional"))
    )
    (net (code "16") (name "LED5") (class "Default")
      (node (ref "R_LED5") (pin "2") (pinfunction "2_2") (pintype "passive"))
      (node (ref "U$3") (pin "16") (pinfunction "PC1_16") (pintype "bidirectional"))
    )
    (net (code "17") (name "LEFT_REC") (class "Default")
      (node (ref "L_REC") (pin "E") (pinfunction "E_E") (pintype "bidirectional"))
      (node (ref "R_L_R") (pin "2") (pinfunction "2_2") (pintype "passive"))
      (node (ref "U$3") (pin "32") (pinfunction "PC4_32") (pintype "bidirectional"))
    )
    (net (code "18") (name "LENCA") (class "Default")
      (node (ref "L_MOT") (pin "1") (pinfunction "1_1") (pintype "passive"))
      (node (ref "U$3") (pin "41") (pinfunction "PE11_41") (pintype "bidirectional"))
    )
    (net (code "19") (name "LENCB") (class "Default")
      (node (ref "L_MOT") (pin "2") (pinfunction "2_2") (pintype "passive"))
      (node (ref "U$3") (pin "39") (pinfunction "PE9_39") (pintype "bidirectional"))
    )
    (net (code "20") (name "LF_EMITTER") (class "Default")
      (node (ref "U$3") (pin "66") (pinfunction "PC9_66") (pintype "bidirectional"))
      (node (ref "U$9") (pin "7B") (pinfunction "7B_7B") (pintype "bidirectional"))
    )
    (net (code "21") (name "LF_REC") (class "Default")
      (node (ref "LF_REC") (pin "E") (pinfunction "E_E") (pintype "bidirectional"))
      (node (ref "R_LF_R") (pin "2") (pinfunction "2_2") (pintype "passive"))
      (node (ref "U$3") (pin "33") (pinfunction "PC5_33") (pintype "bidirectional"))
    )
    (net (code "22") (name "LPWMA") (class "Default")
      (node (ref "MOS_L") (pin "IN_A") (pinfunction "IN_A_IN_A") (pintype "bidirectional"))
      (node (ref "R1_LMOT") (pin "2") (pinfunction "2_2") (pintype "passive"))
      (node (ref "U$3") (pin "24") (pinfunction "PA2_24") (pintype "bidirectional"))
    )
    (net (code "23") (name "LPWMB") (class "Default")
      (node (ref "MOS_L") (pin "IN_B") (pinfunction "IN_B_IN_B") (pintype "bidirectional"))
      (node (ref "R2_LMOT") (pin "2") (pinfunction "2_2") (pintype "passive"))
      (node (ref "U$3") (pin "25") (pinfunction "PA3_25") (pintype "bidirectional"))
    )
    (net (code "24") (name "L_EMITTER") (class "Default")
      (node (ref "U$3") (pin "65") (pinfunction "PC8_65") (pintype "bidirectional"))
      (node (ref "U$9") (pin "5B") (pinfunction "5B_5B") (pintype "bidirectional"))
      (node (ref "U$9") (pin "6B") (pinfunction "6B_6B") (pintype "bidirectional"))
    )
    (net (code "25") (name "Net-(33LDO-NR)") (class "Default")
      (node (ref "33LDO") (pin "4") (pinfunction "NR_4") (pintype "bidirectional"))
      (node (ref "C3_3.3V") (pin "1") (pinfunction "1_1") (pintype "passive"))
    )
    (net (code "26") (name "Net-(G1-AV_DD)") (class "Default")
      (node (ref "C2_G") (pin "1") (pinfunction "1_1") (pintype "passive"))
      (node (ref "G1") (pin "14") (pinfunction "AV_DD_14") (pintype "bidirectional"))
    )
    (net (code "27") (name "Net-(G1-CP5)") (class "Default")
      (node (ref "C3_G") (pin "1") (pinfunction "1_1") (pintype "passive"))
      (node (ref "D_G") (pin "C") (pinfunction "C_C") (pintype "passive"))
      (node (ref "G1") (pin "9") (pinfunction "CP5_9") (pintype "bidirectional"))
    )
    (net (code "28") (name "Net-(G1-DV_DD)") (class "Default")
      (node (ref "C1_G") (pin "1") (pinfunction "1_1") (pintype "passive"))
      (node (ref "G1") (pin "1") (pinfunction "DV_DD_1") (pintype "bidirectional"))
    )
    (net (code "29") (name "Net-(G1-V_X)") (class "Default")
      (node (ref "D_G") (pin "A") (pinfunction "A_A") (pintype "passive"))
      (node (ref "G1") (pin "8") (pinfunction "V_X_8") (pintype "bidirectional"))
      (node (ref "L4") (pin "2") (pinfunction "2_2") (pintype "passive"))
    )
    (net (code "30") (name "Net-(HB_L-PadN1D{slash}P1D)") (class "Default")
      (node (ref "HB_L") (pin "N1D/P1D") (pinfunction "N1D/P1D_N1D/P1D") (pintype "bidirectional"))
      (node (ref "L_MOT") (pin "5") (pinfunction "5_5") (pintype "passive"))
    )
    (net (code "31") (name "Net-(HB_L-PadN1G)") (class "Default")
      (node (ref "HB_L") (pin "N1G") (pinfunction "N1G_N1G") (pintype "bidirectional"))
      (node (ref "MOS_L") (pin "OUT_A") (pinfunction "OUT_A_OUT_A") (pintype "bidirectional"))
    )
    (net (code "32") (name "Net-(HB_L-PadN2D{slash}P2D)") (class "Default")
      (node (ref "HB_L") (pin "N2D/P2D") (pinfunction "N2D/P2D_N2D/P2D") (pintype "bidirectional"))
      (node (ref "L_MOT") (pin "6") (pinfunction "6_6") (pintype "passive"))
    )
    (net (code "33") (name "Net-(HB_L-PadN2G)") (class "Default")
      (node (ref "HB_L") (pin "N2G") (pinfunction "N2G_N2G") (pintype "bidirectional"))
      (node (ref "HB_L") (pin "P2G") (pinfunction "P2G_P2G") (pintype "bidirectional"))
      (node (ref "MOS_L") (pin "OUT_B") (pinfunction "OUT_B_OUT_B") (pintype "bidirectional"))
    )
    (net (code "34") (name "Net-(HB_R-PadN1D{slash}P1D)") (class "Default")
      (node (ref "HB_R") (pin "N1D/P1D") (pinfunction "N1D/P1D_N1D/P1D") (pintype "bidirectional"))
      (node (ref "R_MOT") (pin "5") (pinfunction "5_5") (pintype "passive"))
    )
    (net (code "35") (name "Net-(HB_R-PadN1G)") (class "Default")
      (node (ref "HB_R") (pin "N1G") (pinfunction "N1G_N1G") (pintype "bidirectional"))
      (node (ref "MOS_R") (pin "OUT_A") (pinfunction "OUT_A_OUT_A") (pintype "bidirectional"))
    )
    (net (code "36") (name "Net-(HB_R-PadN2D{slash}P2D)") (class "Default")
      (node (ref "HB_R") (pin "N2D/P2D") (pinfunction "N2D/P2D_N2D/P2D") (pintype "bidirectional"))
      (node (ref "R_MOT") (pin "6") (pinfunction "6_6") (pintype "passive"))
    )
    (net (code "37") (name "Net-(HB_R-PadN2G)") (class "Default")
      (node (ref "HB_R") (pin "N2G") (pinfunction "N2G_N2G") (pintype "bidirectional"))
      (node (ref "HB_R") (pin "P2G") (pinfunction "P2G_P2G") (pintype "bidirectional"))
      (node (ref "MOS_R") (pin "OUT_B") (pinfunction "OUT_B_OUT_B") (pintype "bidirectional"))
    )
    (net (code "38") (name "Net-(LED1-PadA)") (class "Default")
      (node (ref "LED1") (pin "A") (pinfunction "A_A") (pintype "passive"))
      (node (ref "R_LED1") (pin "1") (pinfunction "1_1") (pintype "passive"))
    )
    (net (code "39") (name "Net-(LED2-PadA)") (class "Default")
      (node (ref "LED2") (pin "A") (pinfunction "A_A") (pintype "passive"))
      (node (ref "R_LED2") (pin "1") (pinfunction "1_1") (pintype "passive"))
    )
    (net (code "40") (name "Net-(LED3-PadA)") (class "Default")
      (node (ref "LED3") (pin "A") (pinfunction "A_A") (pintype "passive"))
      (node (ref "R_LED3") (pin "1") (pinfunction "1_1") (pintype "passive"))
    )
    (net (code "41") (name "Net-(LED4-PadA)") (class "Default")
      (node (ref "LED4") (pin "A") (pinfunction "A_A") (pintype "passive"))
      (node (ref "R_LED4") (pin "1") (pinfunction "1_1") (pintype "passive"))
    )
    (net (code "42") (name "Net-(LED5-PadA)") (class "Default")
      (node (ref "LED5") (pin "A") (pinfunction "A_A") (pintype "passive"))
      (node (ref "R_LED5") (pin "1") (pinfunction "1_1") (pintype "passive"))
    )
    (net (code "43") (name "Net-(LF_IR_EMIT-C)") (class "Default")
      (node (ref "LF_IR_EMIT") (pin "K") (pinfunction "C_K") (pintype "passive"))
      (node (ref "R_LF_E") (pin "2") (pinfunction "2_2") (pintype "passive"))
    )
    (net (code "44") (name "Net-(L_IR_EMIT-C)") (class "Default")
      (node (ref "L_IR_EMIT") (pin "K") (pinfunction "C_K") (pintype "passive"))
      (node (ref "R_L_E") (pin "2") (pinfunction "2_2") (pintype "passive"))
    )
    (net (code "45") (name "Net-(PWR_LED-PadA)") (class "Default")
      (node (ref "PWR_LED") (pin "A") (pinfunction "A_A") (pintype "passive"))
      (node (ref "R_PWR") (pin "1") (pinfunction "1_1") (pintype "passive"))
    )
    (net (code "46") (name "Net-(PWR_SWITCH-Pad2)") (class "Default")
      (node (ref "PWR_SWITCH") (pin "2") (pinfunction "2_2") (pintype "bidirectional"))
      (node (ref "U$7") (pin "+") (pinfunction "+_+") (pintype "bidirectional"))
    )
    (net (code "47") (name "Net-(RF_IR_EMIT-C)") (class "Default")
      (node (ref "RF_IR_EMIT") (pin "K") (pinfunction "C_K") (pintype "passive"))
      (node (ref "R_RF_E") (pin "2") (pinfunction "2_2") (pintype "passive"))
    )
    (net (code "48") (name "Net-(R_IR_EMIT-C)") (class "Default")
      (node (ref "R_IR_EMIT") (pin "K") (pinfunction "C_K") (pintype "passive"))
      (node (ref "R_R_E") (pin "2") (pinfunction "2_2") (pintype "passive"))
    )
    (net (code "49") (name "Net-(R_LF_E-Pad1)") (class "Default")
      (node (ref "R_LF_E") (pin "1") (pinfunction "1_1") (pintype "passive"))
      (node (ref "U$9") (pin "3C") (pinfunction "3C_3C") (pintype "bidirectional"))
      (node (ref "U$9") (pin "4C") (pinfunction "4C_4C") (pintype "bidirectional"))
    )
    (net (code "50") (name "Net-(R_L_E-Pad1)") (class "Default")
      (node (ref "R_L_E") (pin "1") (pinfunction "1_1") (pintype "passive"))
      (node (ref "U$9") (pin "2C") (pinfunction "2C_2C") (pintype "bidirectional"))
    )
    (net (code "51") (name "Net-(R_RF_E-Pad1)") (class "Default")
      (node (ref "R_RF_E") (pin "1") (pinfunction "1_1") (pintype "passive"))
      (node (ref "U$9") (pin "5C") (pinfunction "5C_5C") (pintype "bidirectional"))
      (node (ref "U$9") (pin "6C") (pinfunction "6C_6C") (pintype "bidirectional"))
    )
    (net (code "52") (name "Net-(R_R_E-Pad1)") (class "Default")
      (node (ref "R_R_E") (pin "1") (pinfunction "1_1") (pintype "passive"))
      (node (ref "U$9") (pin "7C") (pinfunction "7C_7C") (pintype "bidirectional"))
    )
    (net (code "53") (name "Net-(SPK1--)") (class "Default")
      (node (ref "D_B") (pin "A") (pinfunction "A_A") (pintype "passive"))
      (node (ref "SPK1") (pin "+") (pinfunction "-_+") (pintype "passive"))
      (node (ref "U$9") (pin "1C") (pinfunction "1C_1C") (pintype "bidirectional"))
    )
    (net (code "54") (name "Net-(U$3-VCAP1)") (class "Default")
      (node (ref "C_VCAP1") (pin "1") (pinfunction "1_1") (pintype "passive"))
      (node (ref "U$3") (pin "48") (pinfunction "VCAP1_48") (pintype "bidirectional"))
    )
    (net (code "55") (name "Net-(U$3-VCAP2)") (class "Default")
      (node (ref "C_VCAP2") (pin "1") (pinfunction "1_1") (pintype "passive"))
      (node (ref "U$3") (pin "73") (pinfunction "VCAP2_73") (pintype "bidirectional"))
    )
    (net (code "56") (name "Net-(U$7-Pad-)") (class "Default")
      (node (ref "U$7") (pin "-") (pinfunction "-_-") (pintype "bidirectional"))
      (node (ref "U$8") (pin "+") (pinfunction "+_+") (pintype "bidirectional"))
    )
    (net (code "57") (name "RENCA") (class "Default")
      (node (ref "R_MOT") (pin "1") (pinfunction "1_1") (pintype "passive"))
      (node (ref "U$3") (pin "44") (pinfunction "PE14_44") (pintype "bidirectional"))
    )
    (net (code "58") (name "RENCB") (class "Default")
      (node (ref "R_MOT") (pin "2") (pinfunction "2_2") (pintype "passive"))
      (node (ref "U$3") (pin "43") (pinfunction "PE13_43") (pintype "bidirectional"))
    )
    (net (code "59") (name "RESET") (class "Default")
      (node (ref "C_RESET1") (pin "1") (pinfunction "1_1") (pintype "passive"))
      (node (ref "RST") (pin "1") (pinfunction "S_1") (pintype "passive"))
      (node (ref "R_RST_UP1") (pin "1") (pinfunction "1_1") (pintype "passive"))
      (node (ref "U$3") (pin "14") (pinfunction "NRST_14") (pintype "bidirectional"))
    )
    (net (code "60") (name "RF_EMITTER") (class "Default")
      (node (ref "U$3") (pin "91") (pinfunction "PB5_91") (pintype "bidirectional"))
      (node (ref "U$9") (pin "2B") (pinfunction "2B_2B") (pintype "bidirectional"))
    )
    (net (code "61") (name "RF_REC") (class "Default")
      (node (ref "RF_REC") (pin "E") (pinfunction "E_E") (pintype "bidirectional"))
      (node (ref "R_RF_R") (pin "2") (pinfunction "2_2") (pintype "passive"))
      (node (ref "U$3") (pin "34") (pinfunction "PB0_34") (pintype "bidirectional"))
    )
    (net (code "62") (name "RIGHT_REC") (class "Default")
      (node (ref "R_REC") (pin "E") (pinfunction "E_E") (pintype "bidirectional"))
      (node (ref "R_R_R") (pin "2") (pinfunction "2_2") (pintype "passive"))
      (node (ref "U$3") (pin "35") (pinfunction "PB1_35") (pintype "bidirectional"))
    )
    (net (code "63") (name "RPWMA") (class "Default")
      (node (ref "MOS_R") (pin "IN_A") (pinfunction "IN_A_IN_A") (pintype "bidirectional"))
      (node (ref "R1_RMOT") (pin "2") (pinfunction "2_2") (pintype "passive"))
      (node (ref "U$3") (pin "22") (pinfunction "PA0-WKUP_22") (pintype "bidirectional"))
    )
    (net (code "64") (name "RPWMB") (class "Default")
      (node (ref "MOS_R") (pin "IN_B") (pinfunction "IN_B_IN_B") (pintype "bidirectional"))
      (node (ref "R2_RMOT") (pin "2") (pinfunction "2_2") (pintype "passive"))
      (node (ref "U$3") (pin "23") (pinfunction "PA1_23") (pintype "bidirectional"))
    )
    (net (code "65") (name "RX") (class "Default")
      (node (ref "PROG_HEAD") (pin "5") (pinfunction "5_5") (pintype "passive"))
      (node (ref "U$3") (pin "69") (pinfunction "PA10_69") (pintype "bidirectional"))
    )
    (net (code "66") (name "R_EMITTER") (class "Default")
      (node (ref "U$3") (pin "90") (pinfunction "PB4_90") (pintype "bidirectional"))
      (node (ref "U$9") (pin "3B") (pinfunction "3B_3B") (pintype "bidirectional"))
      (node (ref "U$9") (pin "4B") (pinfunction "4B_4B") (pintype "bidirectional"))
    )
    (net (code "67") (name "SW1") (class "Default")
      (node (ref "C_S1") (pin "1") (pinfunction "1_1") (pintype "passive"))
      (node (ref "R_SW1") (pin "1") (pinfunction "1_1") (pintype "passive"))
      (node (ref "S1") (pin "1") (pinfunction "S_1") (pintype "passive"))
      (node (ref "U$3") (pin "63") (pinfunction "PC6_63") (pintype "bidirectional"))
    )
    (net (code "68") (name "SW2") (class "Default")
      (node (ref "C_S2") (pin "1") (pinfunction "1_1") (pintype "passive"))
      (node (ref "R_SW2") (pin "1") (pinfunction "1_1") (pintype "passive"))
      (node (ref "S2") (pin "1") (pinfunction "S_1") (pintype "passive"))
      (node (ref "U$3") (pin "62") (pinfunction "PD15_62") (pintype "bidirectional"))
    )
    (net (code "69") (name "SWCLK") (class "Default")
      (node (ref "PROG_HEAD") (pin "4") (pinfunction "4_4") (pintype "passive"))
      (node (ref "U$3") (pin "76") (pinfunction "PA14_76") (pintype "bidirectional"))
    )
    (net (code "70") (name "SWDIO") (class "Default")
      (node (ref "PROG_HEAD") (pin "2") (pinfunction "2_2") (pintype "passive"))
      (node (ref "U$3") (pin "72") (pinfunction "PA13_72") (pintype "bidirectional"))
    )
    (net (code "71") (name "TX") (class "Default")
      (node (ref "PROG_HEAD") (pin "7") (pinfunction "7_7") (pintype "passive"))
      (node (ref "U$3") (pin "68") (pinfunction "PA9_68") (pintype "bidirectional"))
    )
    (net (code "72") (name "VOLTMETER") (class "Default")
      (node (ref "R1_VOLT") (pin "1") (pinfunction "1_1") (pintype "passive"))
      (node (ref "R2_VOLT") (pin "2") (pinfunction "2_2") (pintype "passive"))
      (node (ref "U$3") (pin "15") (pinfunction "PC0_15") (pintype "bidirectional"))
    )
    (net (code "73") (name "V_BAT") (class "Default")
      (node (ref "50LDO") (pin "IN1") (pinfunction "IN1_IN1") (pintype "bidirectional"))
      (node (ref "50LDO") (pin "IN2") (pinfunction "IN2_IN2") (pintype "bidirectional"))
      (node (ref "C1_LMOT") (pin "2") (pinfunction "2_2") (pintype "passive"))
      (node (ref "C1_RMOT") (pin "2") (pinfunction "2_2") (pintype "passive"))
      (node (ref "C2_LMOT") (pin "2") (pinfunction "2_2") (pintype "passive"))
      (node (ref "C2_RMOT") (pin "2") (pinfunction "2_2") (pintype "passive"))
      (node (ref "C_VBAT1") (pin "1") (pinfunction "1_1") (pintype "passive"))
      (node (ref "C_VBAT2") (pin "1") (pinfunction "1_1") (pintype "passive"))
      (node (ref "HB_L") (pin "P1S/PS2") (pinfunction "P1S/P2S_P1S/PS2") (pintype "bidirectional"))
      (node (ref "HB_R") (pin "P1S/PS2") (pinfunction "P1S/P2S_P1S/PS2") (pintype "bidirectional"))
      (node (ref "MOS_L") (pin "VDD") (pinfunction "VDD_VDD") (pintype "bidirectional"))
      (node (ref "MOS_R") (pin "VDD") (pinfunction "VDD_VDD") (pintype "bidirectional"))
      (node (ref "PWR_SWITCH") (pin "3") (pinfunction "3_3") (pintype "bidirectional"))
      (node (ref "R1_VOLT") (pin "2") (pinfunction "2_2") (pintype "passive"))
    )
    (net (code "74") (name "unconnected-(50LDO-PadNC)") (class "Default")
      (node (ref "50LDO") (pin "NC") (pinfunction "NC_NC") (pintype "bidirectional"))
    )
    (net (code "75") (name "unconnected-(50LDO-PadPG)") (class "Default")
      (node (ref "50LDO") (pin "PG") (pinfunction "PG_PG") (pintype "bidirectional"))
    )
    (net (code "76") (name "unconnected-(BOOT0-P1-Pad4)") (class "Default")
      (node (ref "BOOT0") (pin "4") (pinfunction "P1_4") (pintype "passive"))
    )
    (net (code "77") (name "unconnected-(BOOT0-S1-Pad2)") (class "Default")
      (node (ref "BOOT0") (pin "2") (pinfunction "S1_2") (pintype "passive"))
    )
    (net (code "78") (name "unconnected-(HB_L-PadP1G)") (class "Default")
      (node (ref "HB_L") (pin "P1G") (pinfunction "P1G_P1G") (pintype "bidirectional"))
    )
    (net (code "79") (name "unconnected-(HB_R-PadP1G)") (class "Default")
      (node (ref "HB_R") (pin "P1G") (pinfunction "P1G_P1G") (pintype "bidirectional"))
    )
    (net (code "80") (name "unconnected-(MOS_L-PadNC1)") (class "Default")
      (node (ref "MOS_L") (pin "NC1") (pinfunction "NC1_NC1") (pintype "bidirectional"))
    )
    (net (code "81") (name "unconnected-(MOS_L-PadNC2)") (class "Default")
      (node (ref "MOS_L") (pin "NC2") (pinfunction "NC2_NC2") (pintype "bidirectional"))
    )
    (net (code "82") (name "unconnected-(MOS_R-PadNC1)") (class "Default")
      (node (ref "MOS_R") (pin "NC1") (pinfunction "NC1_NC1") (pintype "bidirectional"))
    )
    (net (code "83") (name "unconnected-(MOS_R-PadNC2)") (class "Default")
      (node (ref "MOS_R") (pin "NC2") (pinfunction "NC2_NC2") (pintype "bidirectional"))
    )
    (net (code "84") (name "unconnected-(PWR_SWITCH-Pad1)") (class "Default")
      (node (ref "PWR_SWITCH") (pin "1") (pinfunction "1_1") (pintype "bidirectional"))
    )
    (net (code "85") (name "unconnected-(RST-P1-Pad4)") (class "Default")
      (node (ref "RST") (pin "4") (pinfunction "P1_4") (pintype "passive"))
    )
    (net (code "86") (name "unconnected-(RST-S1-Pad2)") (class "Default")
      (node (ref "RST") (pin "2") (pinfunction "S1_2") (pintype "passive"))
    )
    (net (code "87") (name "unconnected-(S1-P1-Pad4)") (class "Default")
      (node (ref "S1") (pin "4") (pinfunction "P1_4") (pintype "passive"))
    )
    (net (code "88") (name "unconnected-(S1-S1-Pad2)") (class "Default")
      (node (ref "S1") (pin "2") (pinfunction "S1_2") (pintype "passive"))
    )
    (net (code "89") (name "unconnected-(S2-P1-Pad4)") (class "Default")
      (node (ref "S2") (pin "4") (pinfunction "P1_4") (pintype "passive"))
    )
    (net (code "90") (name "unconnected-(S2-S1-Pad2)") (class "Default")
      (node (ref "S2") (pin "2") (pinfunction "S1_2") (pintype "passive"))
    )
    (net (code "91") (name "unconnected-(U$3-PA8-Pad67)") (class "Default")
      (node (ref "U$3") (pin "67") (pinfunction "PA8_67") (pintype "bidirectional"))
    )
    (net (code "92") (name "unconnected-(U$3-PA11-Pad70)") (class "Default")
      (node (ref "U$3") (pin "70") (pinfunction "PA11_70") (pintype "bidirectional"))
    )
    (net (code "93") (name "unconnected-(U$3-PA12-Pad71)") (class "Default")
      (node (ref "U$3") (pin "71") (pinfunction "PA12_71") (pintype "bidirectional"))
    )
    (net (code "94") (name "unconnected-(U$3-PA15-Pad77)") (class "Default")
      (node (ref "U$3") (pin "77") (pinfunction "PA15_77") (pintype "bidirectional"))
    )
    (net (code "95") (name "unconnected-(U$3-PB2-Pad36)") (class "Default")
      (node (ref "U$3") (pin "36") (pinfunction "PB2_36") (pintype "bidirectional"))
    )
    (net (code "96") (name "unconnected-(U$3-PB3-Pad89)") (class "Default")
      (node (ref "U$3") (pin "89") (pinfunction "PB3_89") (pintype "bidirectional"))
    )
    (net (code "97") (name "unconnected-(U$3-PB6-Pad92)") (class "Default")
      (node (ref "U$3") (pin "92") (pinfunction "PB6_92") (pintype "bidirectional"))
    )
    (net (code "98") (name "unconnected-(U$3-PB7-Pad93)") (class "Default")
      (node (ref "U$3") (pin "93") (pinfunction "PB7_93") (pintype "bidirectional"))
    )
    (net (code "99") (name "unconnected-(U$3-PB8-Pad95)") (class "Default")
      (node (ref "U$3") (pin "95") (pinfunction "PB8_95") (pintype "bidirectional"))
    )
    (net (code "100") (name "unconnected-(U$3-PB9-Pad96)") (class "Default")
      (node (ref "U$3") (pin "96") (pinfunction "PB9_96") (pintype "bidirectional"))
    )
    (net (code "101") (name "unconnected-(U$3-PB10-Pad46)") (class "Default")
      (node (ref "U$3") (pin "46") (pinfunction "PB10_46") (pintype "bidirectional"))
    )
    (net (code "102") (name "unconnected-(U$3-PB11-Pad47)") (class "Default")
      (node (ref "U$3") (pin "47") (pinfunction "PB11_47") (pintype "bidirectional"))
    )
    (net (code "103") (name "unconnected-(U$3-PB15-Pad54)") (class "Default")
      (node (ref "U$3") (pin "54") (pinfunction "PB15_54") (pintype "bidirectional"))
    )
    (net (code "104") (name "unconnected-(U$3-PC3-Pad18)") (class "Default")
      (node (ref "U$3") (pin "18") (pinfunction "PC3_18") (pintype "bidirectional"))
    )
    (net (code "105") (name "unconnected-(U$3-PC7-Pad64)") (class "Default")
      (node (ref "U$3") (pin "64") (pinfunction "PC7_64") (pintype "bidirectional"))
    )
    (net (code "106") (name "unconnected-(U$3-PC10-Pad78)") (class "Default")
      (node (ref "U$3") (pin "78") (pinfunction "PC10_78") (pintype "bidirectional"))
    )
    (net (code "107") (name "unconnected-(U$3-PC11-Pad79)") (class "Default")
      (node (ref "U$3") (pin "79") (pinfunction "PC11_79") (pintype "bidirectional"))
    )
    (net (code "108") (name "unconnected-(U$3-PC12-Pad80)") (class "Default")
      (node (ref "U$3") (pin "80") (pinfunction "PC12_80") (pintype "bidirectional"))
    )
    (net (code "109") (name "unconnected-(U$3-PC13-ANTI_TAMP-Pad7)") (class "Default")
      (node (ref "U$3") (pin "7") (pinfunction "PC13-ANTI_TAMP_7") (pintype "bidirectional"))
    )
    (net (code "110") (name "unconnected-(U$3-PC14-OSC32_IN-Pad8)") (class "Default")
      (node (ref "U$3") (pin "8") (pinfunction "PC14-OSC32_IN_8") (pintype "bidirectional"))
    )
    (net (code "111") (name "unconnected-(U$3-PC15-OSC32_OUT-Pad9)") (class "Default")
      (node (ref "U$3") (pin "9") (pinfunction "PC15-OSC32_OUT_9") (pintype "bidirectional"))
    )
    (net (code "112") (name "unconnected-(U$3-PD0-Pad81)") (class "Default")
      (node (ref "U$3") (pin "81") (pinfunction "PD0_81") (pintype "bidirectional"))
    )
    (net (code "113") (name "unconnected-(U$3-PD1-Pad82)") (class "Default")
      (node (ref "U$3") (pin "82") (pinfunction "PD1_82") (pintype "bidirectional"))
    )
    (net (code "114") (name "unconnected-(U$3-PD2-Pad83)") (class "Default")
      (node (ref "U$3") (pin "83") (pinfunction "PD2_83") (pintype "bidirectional"))
    )
    (net (code "115") (name "unconnected-(U$3-PD3-Pad84)") (class "Default")
      (node (ref "U$3") (pin "84") (pinfunction "PD3_84") (pintype "bidirectional"))
    )
    (net (code "116") (name "unconnected-(U$3-PD4-Pad85)") (class "Default")
      (node (ref "U$3") (pin "85") (pinfunction "PD4_85") (pintype "bidirectional"))
    )
    (net (code "117") (name "unconnected-(U$3-PD5-Pad86)") (class "Default")
      (node (ref "U$3") (pin "86") (pinfunction "PD5_86") (pintype "bidirectional"))
    )
    (net (code "118") (name "unconnected-(U$3-PD6-Pad87)") (class "Default")
      (node (ref "U$3") (pin "87") (pinfunction "PD6_87") (pintype "bidirectional"))
    )
    (net (code "119") (name "unconnected-(U$3-PD7-Pad88)") (class "Default")
      (node (ref "U$3") (pin "88") (pinfunction "PD7_88") (pintype "bidirectional"))
    )
    (net (code "120") (name "unconnected-(U$3-PD8-Pad55)") (class "Default")
      (node (ref "U$3") (pin "55") (pinfunction "PD8_55") (pintype "bidirectional"))
    )
    (net (code "121") (name "unconnected-(U$3-PD9-Pad56)") (class "Default")
      (node (ref "U$3") (pin "56") (pinfunction "PD9_56") (pintype "bidirectional"))
    )
    (net (code "122") (name "unconnected-(U$3-PD10-Pad57)") (class "Default")
      (node (ref "U$3") (pin "57") (pinfunction "PD10_57") (pintype "bidirectional"))
    )
    (net (code "123") (name "unconnected-(U$3-PD11-Pad58)") (class "Default")
      (node (ref "U$3") (pin "58") (pinfunction "PD11_58") (pintype "bidirectional"))
    )
    (net (code "124") (name "unconnected-(U$3-PD13-Pad60)") (class "Default")
      (node (ref "U$3") (pin "60") (pinfunction "PD13_60") (pintype "bidirectional"))
    )
    (net (code "125") (name "unconnected-(U$3-PD14-Pad61)") (class "Default")
      (node (ref "U$3") (pin "61") (pinfunction "PD14_61") (pintype "bidirectional"))
    )
    (net (code "126") (name "unconnected-(U$3-PE0-Pad97)") (class "Default")
      (node (ref "U$3") (pin "97") (pinfunction "PE0_97") (pintype "bidirectional"))
    )
    (net (code "127") (name "unconnected-(U$3-PE1-Pad98)") (class "Default")
      (node (ref "U$3") (pin "98") (pinfunction "PE1_98") (pintype "bidirectional"))
    )
    (net (code "128") (name "unconnected-(U$3-PE2-Pad1)") (class "Default")
      (node (ref "U$3") (pin "1") (pinfunction "PE2_1") (pintype "bidirectional"))
    )
    (net (code "129") (name "unconnected-(U$3-PE3-Pad2)") (class "Default")
      (node (ref "U$3") (pin "2") (pinfunction "PE3_2") (pintype "bidirectional"))
    )
    (net (code "130") (name "unconnected-(U$3-PE4-Pad3)") (class "Default")
      (node (ref "U$3") (pin "3") (pinfunction "PE4_3") (pintype "bidirectional"))
    )
    (net (code "131") (name "unconnected-(U$3-PE5-Pad4)") (class "Default")
      (node (ref "U$3") (pin "4") (pinfunction "PE5_4") (pintype "bidirectional"))
    )
    (net (code "132") (name "unconnected-(U$3-PE6-Pad5)") (class "Default")
      (node (ref "U$3") (pin "5") (pinfunction "PE6_5") (pintype "bidirectional"))
    )
    (net (code "133") (name "unconnected-(U$3-PE7-Pad37)") (class "Default")
      (node (ref "U$3") (pin "37") (pinfunction "PE7_37") (pintype "bidirectional"))
    )
    (net (code "134") (name "unconnected-(U$3-PE8-Pad38)") (class "Default")
      (node (ref "U$3") (pin "38") (pinfunction "PE8_38") (pintype "bidirectional"))
    )
    (net (code "135") (name "unconnected-(U$3-PE10-Pad40)") (class "Default")
      (node (ref "U$3") (pin "40") (pinfunction "PE10_40") (pintype "bidirectional"))
    )
    (net (code "136") (name "unconnected-(U$3-PE12-Pad42)") (class "Default")
      (node (ref "U$3") (pin "42") (pinfunction "PE12_42") (pintype "bidirectional"))
    )
    (net (code "137") (name "unconnected-(U$3-PE15-Pad45)") (class "Default")
      (node (ref "U$3") (pin "45") (pinfunction "PE15_45") (pintype "bidirectional"))
    )
    (net (code "138") (name "unconnected-(U$3-PH0-OSC_IN-Pad12)") (class "Default")
      (node (ref "U$3") (pin "12") (pinfunction "PH0-OSC_IN_12") (pintype "bidirectional"))
    )
    (net (code "139") (name "unconnected-(U$3-PH1-OSC_OUT-Pad13)") (class "Default")
      (node (ref "U$3") (pin "13") (pinfunction "PH1-OSC_OUT_13") (pintype "bidirectional"))
    )
    (net (code "140") (name "unconnected-(U$9-PadCOM)") (class "Default")
      (node (ref "U$9") (pin "COM") (pinfunction "COM_COM") (pintype "bidirectional"))
    )
  )
)
